# Charger_Control_Board_rev8.net
KiCad netlist of a schematic drawn in EAGLE
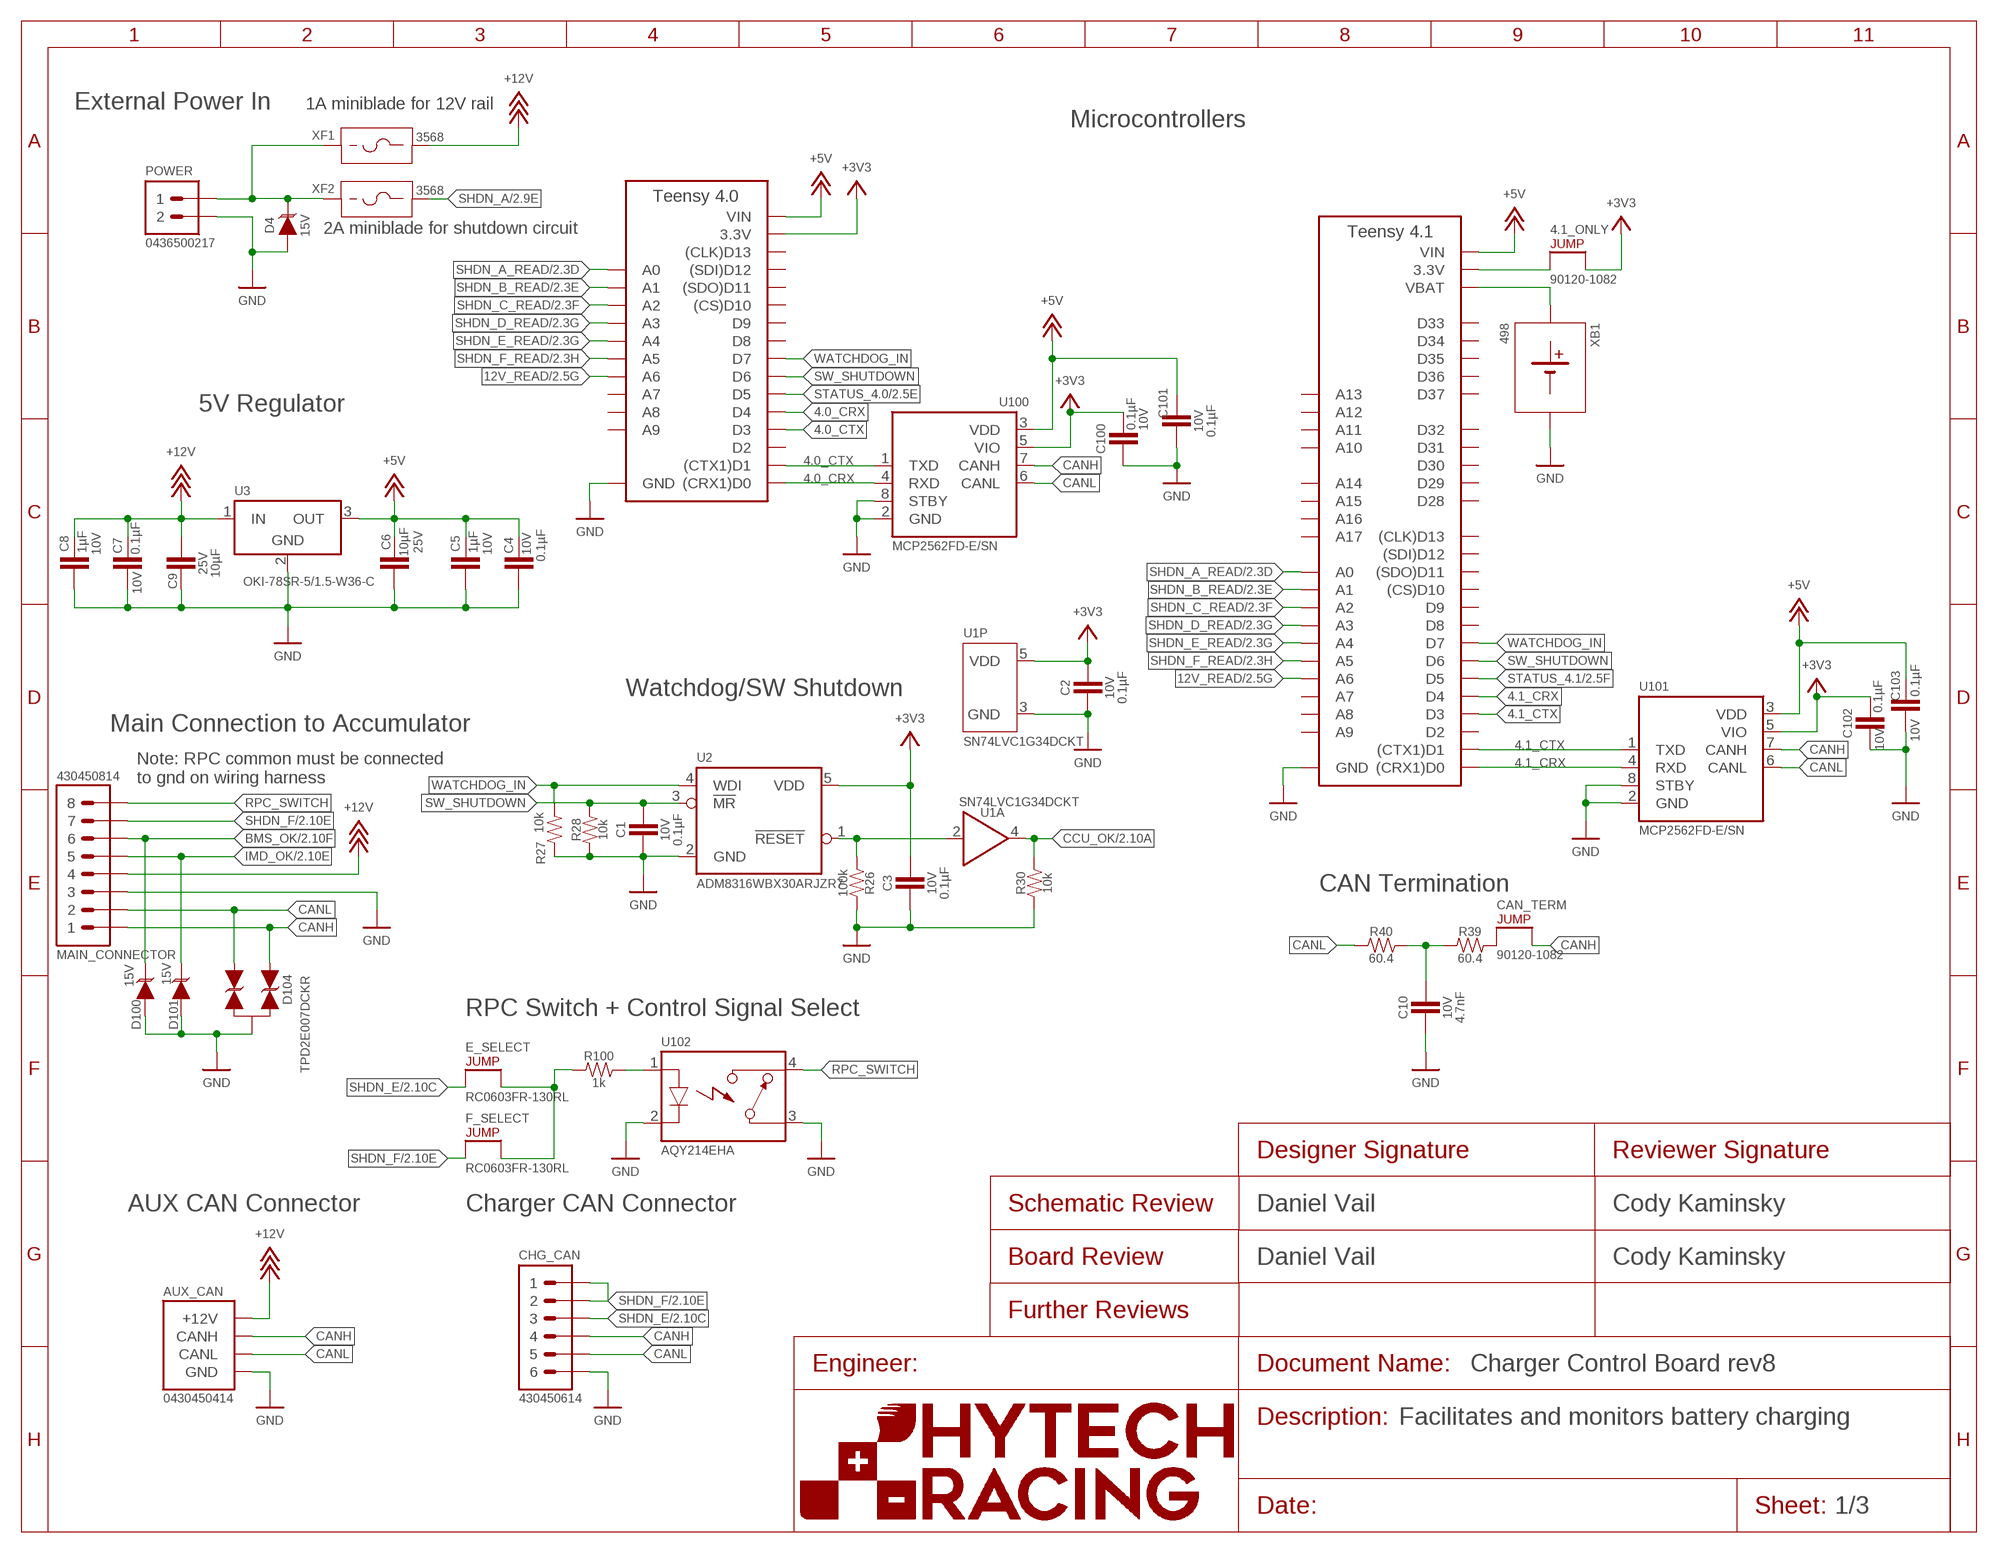
[diagram p0: schematic, sheet 1]
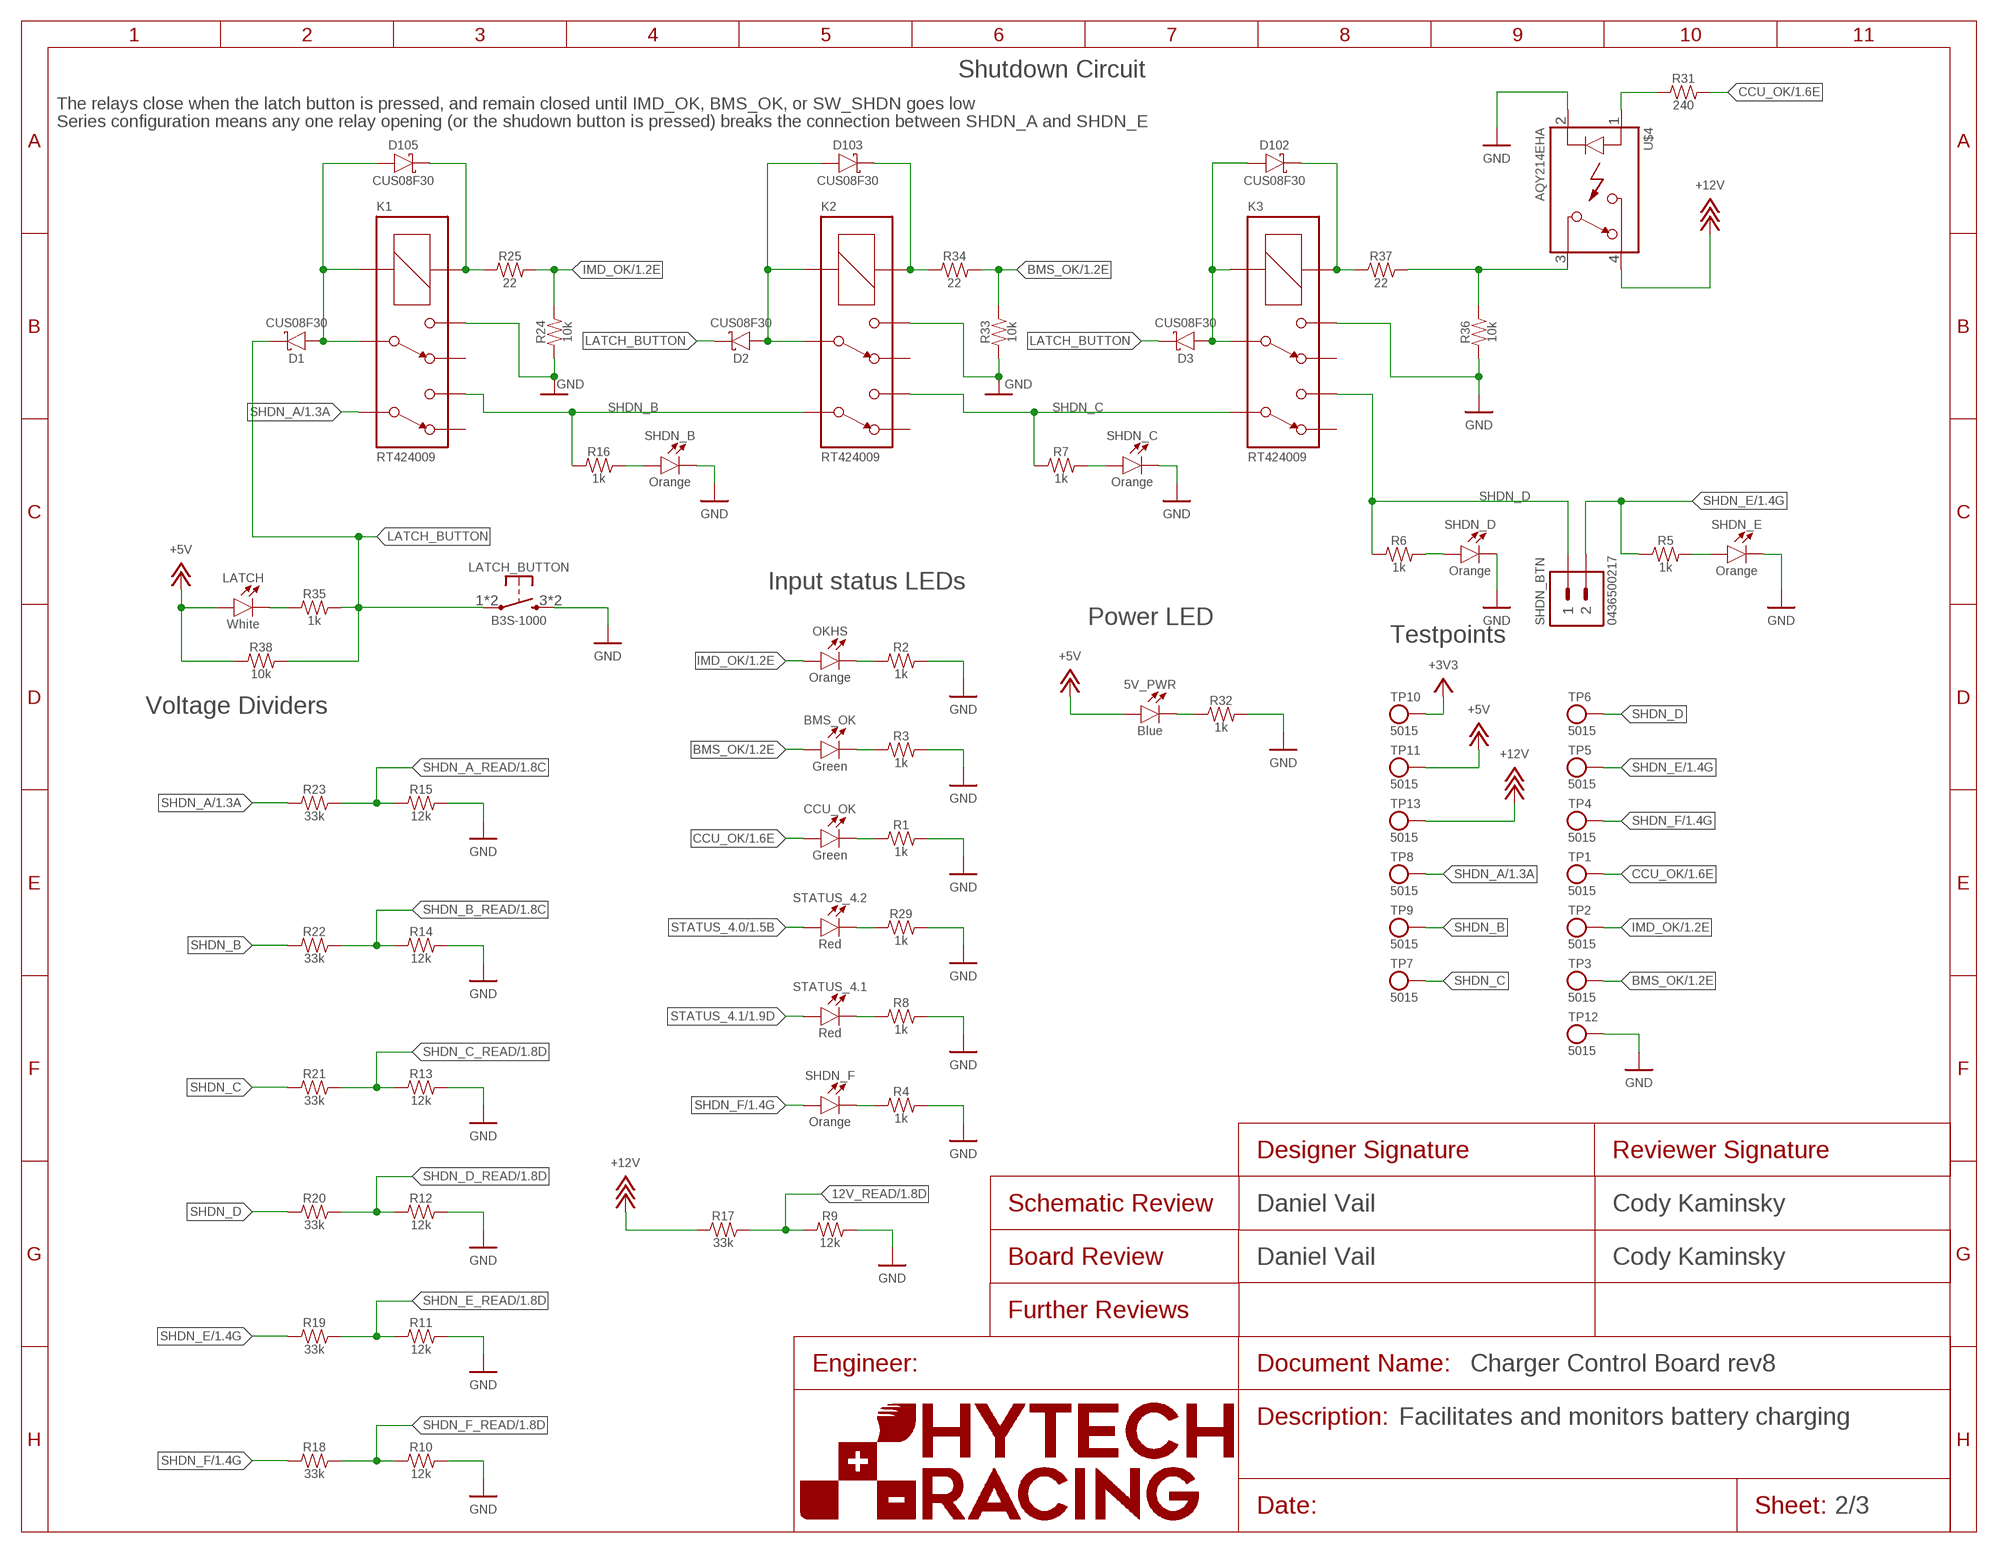
[diagram p1: schematic, sheet 2]
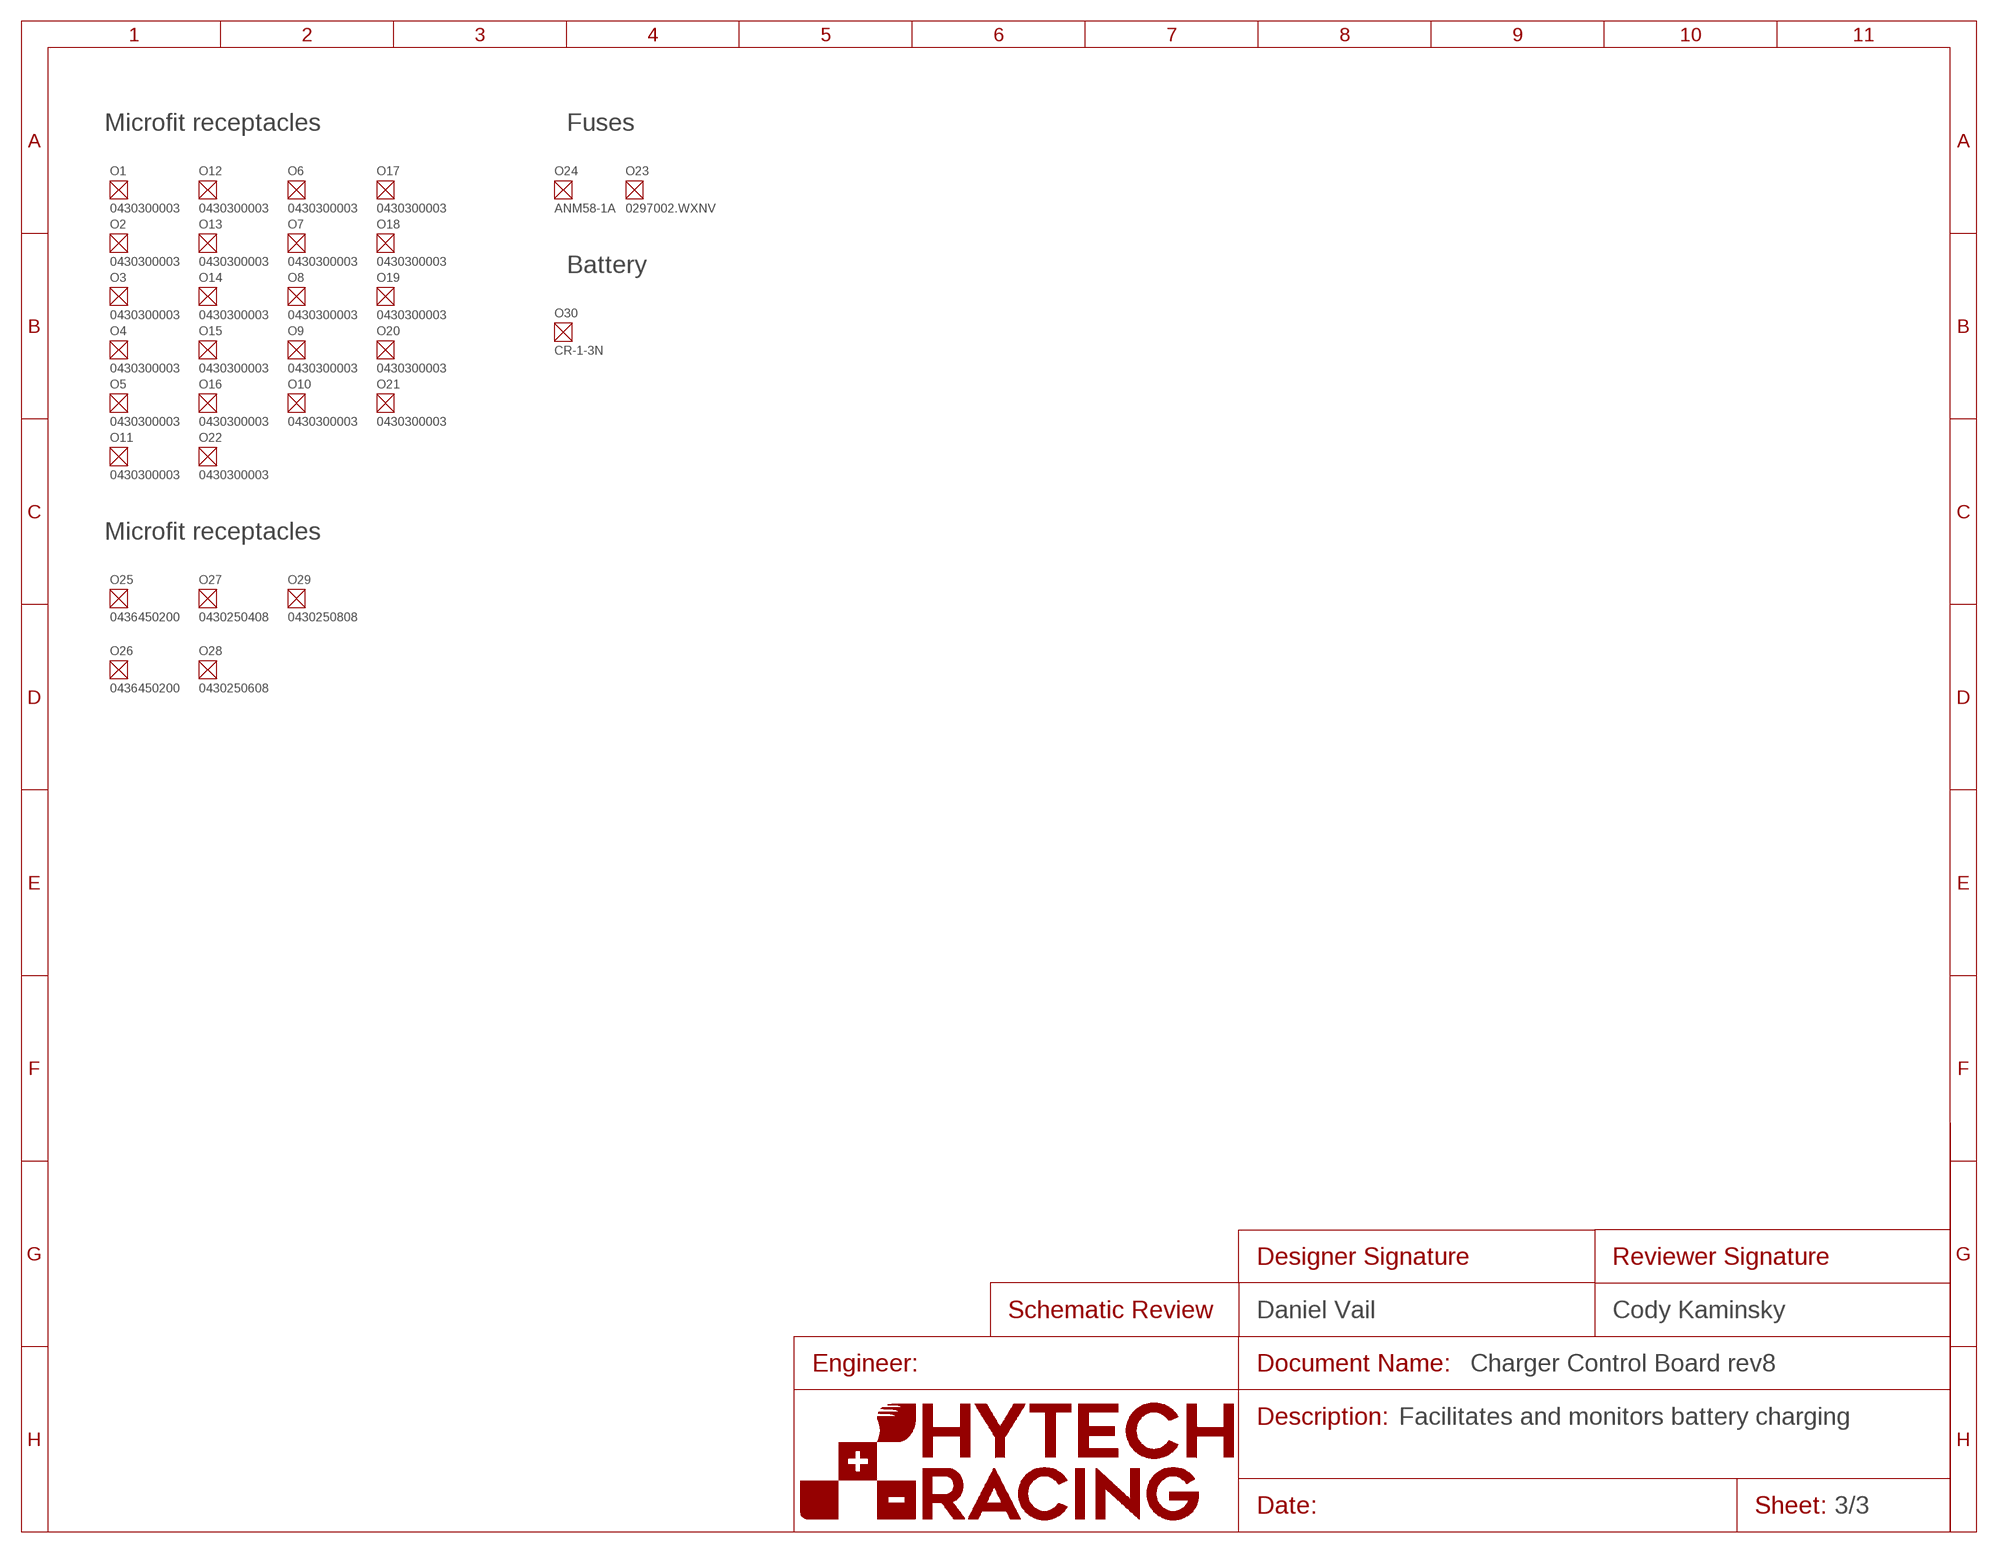
[diagram p2: schematic, sheet 3]

(export (version "E")
  (design (tool "Eeschema 10.0.6"))
  (components
    (comp (ref "5V_PWR")
      (value "LED_0603_BLUE")
      (footprint "eagle-import:0603-LED")
      (fields
        (field (name "COLOR") "Blue")
        (field (name "MANUFACTURER") "Kingbright")
        (field (name "MPN") "APT1608VBC/D")
      )
      (libsource (lib "eagle-import") (part "LED_?_0603BLUE"))
    )
    (comp (ref "BMS_OK")
      (value "LED_0603_GREEN")
      (footprint "eagle-import:0603-LED")
      (fields
        (field (name "COLOR") "Green")
        (field (name "MANUFACTURER") "Kingbright")
        (field (name "MPN") "APT1608ZGCK")
      )
      (libsource (lib "eagle-import") (part "LED_?_0603GREEN"))
    )
    (comp (ref "CCU_OK")
      (value "LED_0603_GREEN")
      (footprint "eagle-import:0603-LED")
      (fields
        (field (name "COLOR") "Green")
        (field (name "MANUFACTURER") "Kingbright")
        (field (name "MPN") "APT1608ZGCK")
      )
      (libsource (lib "eagle-import") (part "LED_?_0603GREEN"))
    )
    (comp (ref "D1")
      (value "SCHOTTKY_SOD323_30V")
      (footprint "eagle-import:SOD-323")
      (fields
        (field (name "MANUFACTURER") "Toshiba Semiconductor and Storage")
        (field (name "MPN") "CUS08F30")
        (field (name "VOLTAGE") "30V")
      )
      (libsource (lib "eagle-import") (part "SCHOTTKY_?_SOD32330V"))
    )
    (comp (ref "D2")
      (value "SCHOTTKY_SOD323_30V")
      (footprint "eagle-import:SOD-323")
      (fields
        (field (name "MANUFACTURER") "Toshiba Semiconductor and Storage")
        (field (name "MPN") "CUS08F30")
        (field (name "VOLTAGE") "30V")
      )
      (libsource (lib "eagle-import") (part "SCHOTTKY_?_SOD32330V"))
    )
    (comp (ref "D3")
      (value "SCHOTTKY_SOD323_30V")
      (footprint "eagle-import:SOD-323")
      (fields
        (field (name "MANUFACTURER") "Toshiba Semiconductor and Storage")
        (field (name "MPN") "CUS08F30")
        (field (name "VOLTAGE") "30V")
      )
      (libsource (lib "eagle-import") (part "SCHOTTKY_?_SOD32330V"))
    )
    (comp (ref "D102")
      (value "SCHOTTKY_SOD323_30V")
      (footprint "eagle-import:SOD-323")
      (fields
        (field (name "MANUFACTURER") "Toshiba Semiconductor and Storage")
        (field (name "MPN") "CUS08F30")
        (field (name "VOLTAGE") "30V")
      )
      (libsource (lib "eagle-import") (part "SCHOTTKY_?_SOD32330V"))
    )
    (comp (ref "D103")
      (value "SCHOTTKY_SOD323_30V")
      (footprint "eagle-import:SOD-323")
      (fields
        (field (name "MANUFACTURER") "Toshiba Semiconductor and Storage")
        (field (name "MPN") "CUS08F30")
        (field (name "VOLTAGE") "30V")
      )
      (libsource (lib "eagle-import") (part "SCHOTTKY_?_SOD32330V"))
    )
    (comp (ref "D105")
      (value "SCHOTTKY_SOD323_30V")
      (footprint "eagle-import:SOD-323")
      (fields
        (field (name "MANUFACTURER") "Toshiba Semiconductor and Storage")
        (field (name "MPN") "CUS08F30")
        (field (name "VOLTAGE") "30V")
      )
      (libsource (lib "eagle-import") (part "SCHOTTKY_?_SOD32330V"))
    )
    (comp (ref "K1")
      (value "RELAY_DPDT")
      (footprint "eagle-import:RT_2_")
      (fields (field (name "MPN") "RT424009") (field (name "MANUFACTURER") "TE Connectivity"))
      (libsource (lib "eagle-import") (part "RELAY_DPDT"))
    )
    (comp (ref "K2")
      (value "RELAY_DPDT")
      (footprint "eagle-import:RT_2_")
      (fields (field (name "MPN") "RT424009") (field (name "MANUFACTURER") "TE Connectivity"))
      (libsource (lib "eagle-import") (part "RELAY_DPDT"))
    )
    (comp (ref "K3")
      (value "RELAY_DPDT")
      (footprint "eagle-import:RT_2_")
      (fields (field (name "MPN") "RT424009") (field (name "MANUFACTURER") "TE Connectivity"))
      (libsource (lib "eagle-import") (part "RELAY_DPDT"))
    )
    (comp (ref "LATCH")
      (value "LED_0603_WHITE")
      (footprint "eagle-import:0603-LED")
      (fields
        (field (name "COLOR") "White")
        (field (name "MANUFACTURER") "Bivar Inc.")
        (field (name "MPN") "SM0603UWC")
      )
      (libsource (lib "eagle-import") (part "LED_?_0603WHITE"))
    )
    (comp (ref "LATCH_BUTTON")
      (value "BUTTON")
      (footprint "eagle-import:B3S-100X")
      (fields (field (name "MPN") "B3S-1000") (field (name "MANUFACTURER") "Omron"))
      (libsource (lib "eagle-import") (part "BUTTON"))
    )
    (comp (ref "OKHS")
      (value "LED_0603_ORANGE")
      (footprint "eagle-import:0603-LED")
      (fields
        (field (name "COLOR") "Orange")
        (field (name "MANUFACTURER") "Kingbright")
        (field (name "MPN") "APT1608SECK")
      )
      (libsource (lib "eagle-import") (part "LED_?_0603ORANGE"))
    )
    (comp (ref "R1")
      (value "RESISTOR_0603_1K")
      (footprint "eagle-import:0603-RES")
      (fields
        (field (name "MANUFACTURER") "Yageo")
        (field (name "MPN") "RC0603FR-071KL")
        (field (name "POWER") "0.1W")
        (field (name "RESISTANCE") "1k")
      )
      (libsource (lib "eagle-import") (part "RESISTOR_?_06031K"))
    )
    (comp (ref "R2")
      (value "RESISTOR_0603_1K")
      (footprint "eagle-import:0603-RES")
      (fields
        (field (name "MANUFACTURER") "Yageo")
        (field (name "MPN") "RC0603FR-071KL")
        (field (name "POWER") "0.1W")
        (field (name "RESISTANCE") "1k")
      )
      (libsource (lib "eagle-import") (part "RESISTOR_?_06031K"))
    )
    (comp (ref "R3")
      (value "RESISTOR_0603_1K")
      (footprint "eagle-import:0603-RES")
      (fields
        (field (name "MANUFACTURER") "Yageo")
        (field (name "MPN") "RC0603FR-071KL")
        (field (name "POWER") "0.1W")
        (field (name "RESISTANCE") "1k")
      )
      (libsource (lib "eagle-import") (part "RESISTOR_?_06031K"))
    )
    (comp (ref "R4")
      (value "RESISTOR_0603_1K")
      (footprint "eagle-import:0603-RES")
      (fields
        (field (name "MANUFACTURER") "Yageo")
        (field (name "MPN") "RC0603FR-071KL")
        (field (name "POWER") "0.1W")
        (field (name "RESISTANCE") "1k")
      )
      (libsource (lib "eagle-import") (part "RESISTOR_?_06031K"))
    )
    (comp (ref "R5")
      (value "RESISTOR_0603_1K")
      (footprint "eagle-import:0603-RES")
      (fields
        (field (name "MANUFACTURER") "Yageo")
        (field (name "MPN") "RC0603FR-071KL")
        (field (name "POWER") "0.1W")
        (field (name "RESISTANCE") "1k")
      )
      (libsource (lib "eagle-import") (part "RESISTOR_?_06031K"))
    )
    (comp (ref "R6")
      (value "RESISTOR_0603_1K")
      (footprint "eagle-import:0603-RES")
      (fields
        (field (name "MANUFACTURER") "Yageo")
        (field (name "MPN") "RC0603FR-071KL")
        (field (name "POWER") "0.1W")
        (field (name "RESISTANCE") "1k")
      )
      (libsource (lib "eagle-import") (part "RESISTOR_?_06031K"))
    )
    (comp (ref "R7")
      (value "RESISTOR_0603_1K")
      (footprint "eagle-import:0603-RES")
      (fields
        (field (name "MANUFACTURER") "Yageo")
        (field (name "MPN") "RC0603FR-071KL")
        (field (name "POWER") "0.1W")
        (field (name "RESISTANCE") "1k")
      )
      (libsource (lib "eagle-import") (part "RESISTOR_?_06031K"))
    )
    (comp (ref "R8")
      (value "RESISTOR_0603_1K")
      (footprint "eagle-import:0603-RES")
      (fields
        (field (name "MANUFACTURER") "Yageo")
        (field (name "MPN") "RC0603FR-071KL")
        (field (name "POWER") "0.1W")
        (field (name "RESISTANCE") "1k")
      )
      (libsource (lib "eagle-import") (part "RESISTOR_?_06031K"))
    )
    (comp (ref "R9")
      (value "RESISTOR_0603_12K")
      (footprint "eagle-import:0603-RES")
      (fields
        (field (name "MANUFACTURER") "Yageo")
        (field (name "MPN") "RC0603FR-0712KL")
        (field (name "POWER") "0.1W")
        (field (name "RESISTANCE") "12k")
      )
      (libsource (lib "eagle-import") (part "RESISTOR_?_060312K"))
    )
    (comp (ref "R10")
      (value "RESISTOR_0603_12K")
      (footprint "eagle-import:0603-RES")
      (fields
        (field (name "MANUFACTURER") "Yageo")
        (field (name "MPN") "RC0603FR-0712KL")
        (field (name "POWER") "0.1W")
        (field (name "RESISTANCE") "12k")
      )
      (libsource (lib "eagle-import") (part "RESISTOR_?_060312K"))
    )
    (comp (ref "R11")
      (value "RESISTOR_0603_12K")
      (footprint "eagle-import:0603-RES")
      (fields
        (field (name "MANUFACTURER") "Yageo")
        (field (name "MPN") "RC0603FR-0712KL")
        (field (name "POWER") "0.1W")
        (field (name "RESISTANCE") "12k")
      )
      (libsource (lib "eagle-import") (part "RESISTOR_?_060312K"))
    )
    (comp (ref "R12")
      (value "RESISTOR_0603_12K")
      (footprint "eagle-import:0603-RES")
      (fields
        (field (name "MANUFACTURER") "Yageo")
        (field (name "MPN") "RC0603FR-0712KL")
        (field (name "POWER") "0.1W")
        (field (name "RESISTANCE") "12k")
      )
      (libsource (lib "eagle-import") (part "RESISTOR_?_060312K"))
    )
    (comp (ref "R13")
      (value "RESISTOR_0603_12K")
      (footprint "eagle-import:0603-RES")
      (fields
        (field (name "MANUFACTURER") "Yageo")
        (field (name "MPN") "RC0603FR-0712KL")
        (field (name "POWER") "0.1W")
        (field (name "RESISTANCE") "12k")
      )
      (libsource (lib "eagle-import") (part "RESISTOR_?_060312K"))
    )
    (comp (ref "R14")
      (value "RESISTOR_0603_12K")
      (footprint "eagle-import:0603-RES")
      (fields
        (field (name "MANUFACTURER") "Yageo")
        (field (name "MPN") "RC0603FR-0712KL")
        (field (name "POWER") "0.1W")
        (field (name "RESISTANCE") "12k")
      )
      (libsource (lib "eagle-import") (part "RESISTOR_?_060312K"))
    )
    (comp (ref "R15")
      (value "RESISTOR_0603_12K")
      (footprint "eagle-import:0603-RES")
      (fields
        (field (name "MANUFACTURER") "Yageo")
        (field (name "MPN") "RC0603FR-0712KL")
        (field (name "POWER") "0.1W")
        (field (name "RESISTANCE") "12k")
      )
      (libsource (lib "eagle-import") (part "RESISTOR_?_060312K"))
    )
    (comp (ref "R16")
      (value "RESISTOR_0603_1K")
      (footprint "eagle-import:0603-RES")
      (fields
        (field (name "MANUFACTURER") "Yageo")
        (field (name "MPN") "RC0603FR-071KL")
        (field (name "POWER") "0.1W")
        (field (name "RESISTANCE") "1k")
      )
      (libsource (lib "eagle-import") (part "RESISTOR_?_06031K"))
    )
    (comp (ref "R17")
      (value "RESISTOR_0603_33K")
      (footprint "eagle-import:0603-RES")
      (fields
        (field (name "MANUFACTURER") "Yageo")
        (field (name "MPN") "RC0603FR-0733KL")
        (field (name "POWER") "0.1W")
        (field (name "RESISTANCE") "33k")
      )
      (libsource (lib "eagle-import") (part "RESISTOR_?_060333K"))
    )
    (comp (ref "R18")
      (value "RESISTOR_0603_33K")
      (footprint "eagle-import:0603-RES")
      (fields
        (field (name "MANUFACTURER") "Yageo")
        (field (name "MPN") "RC0603FR-0733KL")
        (field (name "POWER") "0.1W")
        (field (name "RESISTANCE") "33k")
      )
      (libsource (lib "eagle-import") (part "RESISTOR_?_060333K"))
    )
    (comp (ref "R19")
      (value "RESISTOR_0603_33K")
      (footprint "eagle-import:0603-RES")
      (fields
        (field (name "MANUFACTURER") "Yageo")
        (field (name "MPN") "RC0603FR-0733KL")
        (field (name "POWER") "0.1W")
        (field (name "RESISTANCE") "33k")
      )
      (libsource (lib "eagle-import") (part "RESISTOR_?_060333K"))
    )
    (comp (ref "R20")
      (value "RESISTOR_0603_33K")
      (footprint "eagle-import:0603-RES")
      (fields
        (field (name "MANUFACTURER") "Yageo")
        (field (name "MPN") "RC0603FR-0733KL")
        (field (name "POWER") "0.1W")
        (field (name "RESISTANCE") "33k")
      )
      (libsource (lib "eagle-import") (part "RESISTOR_?_060333K"))
    )
    (comp (ref "R21")
      (value "RESISTOR_0603_33K")
      (footprint "eagle-import:0603-RES")
      (fields
        (field (name "MANUFACTURER") "Yageo")
        (field (name "MPN") "RC0603FR-0733KL")
        (field (name "POWER") "0.1W")
        (field (name "RESISTANCE") "33k")
      )
      (libsource (lib "eagle-import") (part "RESISTOR_?_060333K"))
    )
    (comp (ref "R22")
      (value "RESISTOR_0603_33K")
      (footprint "eagle-import:0603-RES")
      (fields
        (field (name "MANUFACTURER") "Yageo")
        (field (name "MPN") "RC0603FR-0733KL")
        (field (name "POWER") "0.1W")
        (field (name "RESISTANCE") "33k")
      )
      (libsource (lib "eagle-import") (part "RESISTOR_?_060333K"))
    )
    (comp (ref "R23")
      (value "RESISTOR_0603_33K")
      (footprint "eagle-import:0603-RES")
      (fields
        (field (name "MANUFACTURER") "Yageo")
        (field (name "MPN") "RC0603FR-0733KL")
        (field (name "POWER") "0.1W")
        (field (name "RESISTANCE") "33k")
      )
      (libsource (lib "eagle-import") (part "RESISTOR_?_060333K"))
    )
    (comp (ref "R24")
      (value "RESISTOR_0603_10K")
      (footprint "eagle-import:0603-RES")
      (fields
        (field (name "MANUFACTURER") "Yageo")
        (field (name "MPN") "RC0603FR-0710KL")
        (field (name "POWER") "0.1W")
        (field (name "RESISTANCE") "10k")
      )
      (libsource (lib "eagle-import") (part "RESISTOR_?_060310K"))
    )
    (comp (ref "R25")
      (value "RESISTOR_0603_22")
      (footprint "eagle-import:0603-RES")
      (fields
        (field (name "MANUFACTURER") "Yageo")
        (field (name "MPN") "RC0603FR-0722RL")
        (field (name "POWER") "0.1W")
        (field (name "RESISTANCE") "22")
      )
      (libsource (lib "eagle-import") (part "RESISTOR_?_060322"))
    )
    (comp (ref "R29")
      (value "RESISTOR_0603_1K")
      (footprint "eagle-import:0603-RES")
      (fields
        (field (name "MANUFACTURER") "Yageo")
        (field (name "MPN") "RC0603FR-071KL")
        (field (name "POWER") "0.1W")
        (field (name "RESISTANCE") "1k")
      )
      (libsource (lib "eagle-import") (part "RESISTOR_?_06031K"))
    )
    (comp (ref "R31")
      (value "RESISTOR_0603_240")
      (footprint "eagle-import:0603-RES")
      (fields
        (field (name "MANUFACTURER") "Yageo")
        (field (name "MPN") "RC0603FR-07240RL")
        (field (name "POWER") "0.1W")
        (field (name "RESISTANCE") "240")
      )
      (libsource (lib "eagle-import") (part "RESISTOR_?_0603240"))
    )
    (comp (ref "R32")
      (value "RESISTOR_0603_1K")
      (footprint "eagle-import:0603-RES")
      (fields
        (field (name "MANUFACTURER") "Yageo")
        (field (name "MPN") "RC0603FR-071KL")
        (field (name "POWER") "0.1W")
        (field (name "RESISTANCE") "1k")
      )
      (libsource (lib "eagle-import") (part "RESISTOR_?_06031K"))
    )
    (comp (ref "R33")
      (value "RESISTOR_0603_10K")
      (footprint "eagle-import:0603-RES")
      (fields
        (field (name "MANUFACTURER") "Yageo")
        (field (name "MPN") "RC0603FR-0710KL")
        (field (name "POWER") "0.1W")
        (field (name "RESISTANCE") "10k")
      )
      (libsource (lib "eagle-import") (part "RESISTOR_?_060310K"))
    )
    (comp (ref "R34")
      (value "RESISTOR_0603_22")
      (footprint "eagle-import:0603-RES")
      (fields
        (field (name "MANUFACTURER") "Yageo")
        (field (name "MPN") "RC0603FR-0722RL")
        (field (name "POWER") "0.1W")
        (field (name "RESISTANCE") "22")
      )
      (libsource (lib "eagle-import") (part "RESISTOR_?_060322"))
    )
    (comp (ref "R35")
      (value "RESISTOR_0603_1K")
      (footprint "eagle-import:0603-RES")
      (fields
        (field (name "MANUFACTURER") "Yageo")
        (field (name "MPN") "RC0603FR-071KL")
        (field (name "POWER") "0.1W")
        (field (name "RESISTANCE") "1k")
      )
      (libsource (lib "eagle-import") (part "RESISTOR_?_06031K"))
    )
    (comp (ref "R36")
      (value "RESISTOR_0603_10K")
      (footprint "eagle-import:0603-RES")
      (fields
        (field (name "MANUFACTURER") "Yageo")
        (field (name "MPN") "RC0603FR-0710KL")
        (field (name "POWER") "0.1W")
        (field (name "RESISTANCE") "10k")
      )
      (libsource (lib "eagle-import") (part "RESISTOR_?_060310K"))
    )
    (comp (ref "R37")
      (value "RESISTOR_0603_22")
      (footprint "eagle-import:0603-RES")
      (fields
        (field (name "MANUFACTURER") "Yageo")
        (field (name "MPN") "RC0603FR-0722RL")
        (field (name "POWER") "0.1W")
        (field (name "RESISTANCE") "22")
      )
      (libsource (lib "eagle-import") (part "RESISTOR_?_060322"))
    )
    (comp (ref "R38")
      (value "RESISTOR_0603_10K")
      (footprint "eagle-import:0603-RES")
      (fields
        (field (name "MANUFACTURER") "Yageo")
        (field (name "MPN") "RC0603FR-0710KL")
        (field (name "POWER") "0.1W")
        (field (name "RESISTANCE") "10k")
      )
      (libsource (lib "eagle-import") (part "RESISTOR_?_060310K"))
    )
    (comp (ref "SHDN_B")
      (value "LED_0603_ORANGE")
      (footprint "eagle-import:0603-LED")
      (fields
        (field (name "COLOR") "Orange")
        (field (name "MANUFACTURER") "Kingbright")
        (field (name "MPN") "APT1608SECK")
      )
      (libsource (lib "eagle-import") (part "LED_?_0603ORANGE"))
    )
    (comp (ref "SHDN_BTN")
      (value "CONNECTOR-2_MF_T_V_")
      (footprint "eagle-import:MOLEX_MICROFIT_PTH_VERTICAL_02_SINGLE")
      (fields (field (name "MANUFACTURER") "Molex") (field (name "MPN") "0436500217"))
      (libsource (lib "eagle-import") (part "CONNECTOR-2_?_MF_T_VBLACK"))
    )
    (comp (ref "SHDN_C")
      (value "LED_0603_ORANGE")
      (footprint "eagle-import:0603-LED")
      (fields
        (field (name "COLOR") "Orange")
        (field (name "MANUFACTURER") "Kingbright")
        (field (name "MPN") "APT1608SECK")
      )
      (libsource (lib "eagle-import") (part "LED_?_0603ORANGE"))
    )
    (comp (ref "SHDN_D")
      (value "LED_0603_ORANGE")
      (footprint "eagle-import:0603-LED")
      (fields
        (field (name "COLOR") "Orange")
        (field (name "MANUFACTURER") "Kingbright")
        (field (name "MPN") "APT1608SECK")
      )
      (libsource (lib "eagle-import") (part "LED_?_0603ORANGE"))
    )
    (comp (ref "SHDN_E")
      (value "LED_0603_ORANGE")
      (footprint "eagle-import:0603-LED")
      (fields
        (field (name "COLOR") "Orange")
        (field (name "MANUFACTURER") "Kingbright")
        (field (name "MPN") "APT1608SECK")
      )
      (libsource (lib "eagle-import") (part "LED_?_0603ORANGE"))
    )
    (comp (ref "SHDN_F")
      (value "LED_0603_ORANGE")
      (footprint "eagle-import:0603-LED")
      (fields
        (field (name "COLOR") "Orange")
        (field (name "MANUFACTURER") "Kingbright")
        (field (name "MPN") "APT1608SECK")
      )
      (libsource (lib "eagle-import") (part "LED_?_0603ORANGE"))
    )
    (comp (ref "STATUS_4.1")
      (value "LED_0603_RED")
      (footprint "eagle-import:0603-LED")
      (fields
        (field (name "COLOR") "Red")
        (field (name "MANUFACTURER") "Kingbright")
        (field (name "MPN") "APT1608SECK/J3-PRV")
      )
      (libsource (lib "eagle-import") (part "LED_?_0603RED"))
    )
    (comp (ref "STATUS_4.2")
      (value "LED_0603_RED")
      (footprint "eagle-import:0603-LED")
      (fields
        (field (name "COLOR") "Red")
        (field (name "MANUFACTURER") "Kingbright")
        (field (name "MPN") "APT1608SECK/J3-PRV")
      )
      (libsource (lib "eagle-import") (part "LED_?_0603RED"))
    )
    (comp (ref "TP1")
      (value "TEST_POINT")
      (footprint "eagle-import:5015")
      (fields (field (name "MPN") "5015") (field (name "MANUFACTURER") "Keystone Electronics"))
      (libsource (lib "eagle-import") (part "TEST_POINT"))
    )
    (comp (ref "TP2")
      (value "TEST_POINT")
      (footprint "eagle-import:5015")
      (fields (field (name "MPN") "5015") (field (name "MANUFACTURER") "Keystone Electronics"))
      (libsource (lib "eagle-import") (part "TEST_POINT"))
    )
    (comp (ref "TP3")
      (value "TEST_POINT")
      (footprint "eagle-import:5015")
      (fields (field (name "MPN") "5015") (field (name "MANUFACTURER") "Keystone Electronics"))
      (libsource (lib "eagle-import") (part "TEST_POINT"))
    )
    (comp (ref "TP4")
      (value "TEST_POINT")
      (footprint "eagle-import:5015")
      (fields (field (name "MPN") "5015") (field (name "MANUFACTURER") "Keystone Electronics"))
      (libsource (lib "eagle-import") (part "TEST_POINT"))
    )
    (comp (ref "TP5")
      (value "TEST_POINT")
      (footprint "eagle-import:5015")
      (fields (field (name "MPN") "5015") (field (name "MANUFACTURER") "Keystone Electronics"))
      (libsource (lib "eagle-import") (part "TEST_POINT"))
    )
    (comp (ref "TP6")
      (value "TEST_POINT")
      (footprint "eagle-import:5015")
      (fields (field (name "MPN") "5015") (field (name "MANUFACTURER") "Keystone Electronics"))
      (libsource (lib "eagle-import") (part "TEST_POINT"))
    )
    (comp (ref "TP7")
      (value "TEST_POINT")
      (footprint "eagle-import:5015")
      (fields (field (name "MPN") "5015") (field (name "MANUFACTURER") "Keystone Electronics"))
      (libsource (lib "eagle-import") (part "TEST_POINT"))
    )
    (comp (ref "TP8")
      (value "TEST_POINT")
      (footprint "eagle-import:5015")
      (fields (field (name "MPN") "5015") (field (name "MANUFACTURER") "Keystone Electronics"))
      (libsource (lib "eagle-import") (part "TEST_POINT"))
    )
    (comp (ref "TP9")
      (value "TEST_POINT")
      (footprint "eagle-import:5015")
      (fields (field (name "MPN") "5015") (field (name "MANUFACTURER") "Keystone Electronics"))
      (libsource (lib "eagle-import") (part "TEST_POINT"))
    )
    (comp (ref "TP10")
      (value "TEST_POINT")
      (footprint "eagle-import:5015")
      (fields (field (name "MPN") "5015") (field (name "MANUFACTURER") "Keystone Electronics"))
      (libsource (lib "eagle-import") (part "TEST_POINT"))
    )
    (comp (ref "TP11")
      (value "TEST_POINT")
      (footprint "eagle-import:5015")
      (fields (field (name "MPN") "5015") (field (name "MANUFACTURER") "Keystone Electronics"))
      (libsource (lib "eagle-import") (part "TEST_POINT"))
    )
    (comp (ref "TP12")
      (value "TEST_POINT")
      (footprint "eagle-import:5015")
      (fields (field (name "MPN") "5015") (field (name "MANUFACTURER") "Keystone Electronics"))
      (libsource (lib "eagle-import") (part "TEST_POINT"))
    )
    (comp (ref "TP13")
      (value "TEST_POINT")
      (footprint "eagle-import:5015")
      (fields (field (name "MPN") "5015") (field (name "MANUFACTURER") "Keystone Electronics"))
      (libsource (lib "eagle-import") (part "TEST_POINT"))
    )
    (comp (ref "U$4")
      (value "RELAY_SOLIDSTATE_NO")
      (footprint "eagle-import:DIP-4")
      (fields (field (name "MPN") "AQY214EHA") (field (name "MANUFACTURER") "AQY214EHA"))
      (libsource (lib "eagle-import") (part "RELAY_SOLIDSTATE_NO"))
    )
    (comp (ref "4.1_ONLY")
      (value "JUMPER__1X02")
      (footprint "eagle-import:1X02")
      (fields (field (name "MANUFACTURER") "Molex") (field (name "MPN") "90120-1082 "))
      (libsource (lib "eagle-import") (part "JUMPER_?_1X02"))
    )
    (comp (ref "A1")
      (value "TEENSY_4.1")
      (footprint "eagle-import:TEENSY_LONG_EXT")
      (libsource (lib "eagle-import") (part "TEENSY_4.1"))
    )
    (comp (ref "A2")
      (value "TEENSY_4.0")
      (footprint "eagle-import:TEENSY_SHORT")
      (libsource (lib "eagle-import") (part "TEENSY_4.0"))
    )
    (comp (ref "AUX_CAN")
      (value "CONNECTOR-CAN_MF_T_V_BLACK")
      (footprint "eagle-import:MOLEX_MICROFIT_PTH_VERTICAL_04_DUAL")
      (fields (field (name "MANUFACTURER") "Molex") (field (name "MPN") "0430450414"))
      (libsource (lib "eagle-import") (part "CONNECTOR-CAN_?_MF_T_VBLACK"))
    )
    (comp (ref "C1")
      (value "CAPACITOR_0603_10V_0.1UF")
      (footprint "eagle-import:0603-CAP")
      (fields
        (field (name "CAPACITANCE") "0.1µF")
        (field (name "MANUFACTURER") "Vishay Vitramon")
        (field (name "MPN") "VJ0603Y104JXQPW1BC")
        (field (name "TOLERANCE") "5%")
        (field (name "VOLTAGE") "10V")
      )
      (libsource (lib "eagle-import") (part "CAPACITOR_?_060310V_0.1UF"))
    )
    (comp (ref "C2")
      (value "CAPACITOR_0603_10V_0.1UF")
      (footprint "eagle-import:0603-CAP")
      (fields
        (field (name "CAPACITANCE") "0.1µF")
        (field (name "MANUFACTURER") "Vishay Vitramon")
        (field (name "MPN") "VJ0603Y104JXQPW1BC")
        (field (name "TOLERANCE") "5%")
        (field (name "VOLTAGE") "10V")
      )
      (libsource (lib "eagle-import") (part "CAPACITOR_?_060310V_0.1UF"))
    )
    (comp (ref "C3")
      (value "CAPACITOR_0603_10V_0.1UF")
      (footprint "eagle-import:0603-CAP")
      (fields
        (field (name "CAPACITANCE") "0.1µF")
        (field (name "MANUFACTURER") "Vishay Vitramon")
        (field (name "MPN") "VJ0603Y104JXQPW1BC")
        (field (name "TOLERANCE") "5%")
        (field (name "VOLTAGE") "10V")
      )
      (libsource (lib "eagle-import") (part "CAPACITOR_?_060310V_0.1UF"))
    )
    (comp (ref "C4")
      (value "CAPACITOR_0603_10V_0.1UF")
      (footprint "eagle-import:0603-CAP")
      (fields
        (field (name "CAPACITANCE") "0.1µF")
        (field (name "MANUFACTURER") "Vishay Vitramon")
        (field (name "MPN") "VJ0603Y104JXQPW1BC")
        (field (name "TOLERANCE") "5%")
        (field (name "VOLTAGE") "10V")
      )
      (libsource (lib "eagle-import") (part "CAPACITOR_?_060310V_0.1UF"))
    )
    (comp (ref "C5")
      (value "CAPACITOR_0603_10V_1UF")
      (footprint "eagle-import:0603-CAP")
      (fields
        (field (name "CAPACITANCE") "1µF")
        (field (name "MANUFACTURER") "Yageo")
        (field (name "MPN") "CC0603KRX7R6BB105")
        (field (name "TOLERANCE") "10%")
        (field (name "VOLTAGE") "10V")
      )
      (libsource (lib "eagle-import") (part "CAPACITOR_?_060310V_1UF"))
    )
    (comp (ref "C6")
      (value "CAPACITOR_0603_25V_10UF")
      (footprint "eagle-import:0603-CAP")
      (fields
        (field (name "CAPACITANCE") "10µF")
        (field (name "MANUFACTURER") "Murata Electronics")
        (field (name "MPN") "GRM188R61E106MA73D")
        (field (name "TOLERANCE") "20%")
        (field (name "VOLTAGE") "25V")
      )
      (libsource (lib "eagle-import") (part "CAPACITOR_?_060325V_10UF"))
    )
    (comp (ref "C7")
      (value "CAPACITOR_0603_10V_0.1UF")
      (footprint "eagle-import:0603-CAP")
      (fields
        (field (name "CAPACITANCE") "0.1µF")
        (field (name "MANUFACTURER") "Vishay Vitramon")
        (field (name "MPN") "VJ0603Y104JXQPW1BC")
        (field (name "TOLERANCE") "5%")
        (field (name "VOLTAGE") "10V")
      )
      (libsource (lib "eagle-import") (part "CAPACITOR_?_060310V_0.1UF"))
    )
    (comp (ref "C8")
      (value "CAPACITOR_0603_10V_1UF")
      (footprint "eagle-import:0603-CAP")
      (fields
        (field (name "CAPACITANCE") "1µF")
        (field (name "MANUFACTURER") "Yageo")
        (field (name "MPN") "CC0603KRX7R6BB105")
        (field (name "TOLERANCE") "10%")
        (field (name "VOLTAGE") "10V")
      )
      (libsource (lib "eagle-import") (part "CAPACITOR_?_060310V_1UF"))
    )
    (comp (ref "C9")
      (value "CAPACITOR_0603_25V_10UF")
      (footprint "eagle-import:0603-CAP")
      (fields
        (field (name "CAPACITANCE") "10µF")
        (field (name "MANUFACTURER") "Murata Electronics")
        (field (name "MPN") "GRM188R61E106MA73D")
        (field (name "TOLERANCE") "20%")
        (field (name "VOLTAGE") "25V")
      )
      (libsource (lib "eagle-import") (part "CAPACITOR_?_060325V_10UF"))
    )
    (comp (ref "C10")
      (value "CAPACITOR_0603_10V_4.7NF")
      (footprint "eagle-import:0603-CAP")
      (fields
        (field (name "CAPACITANCE") "4.7nF")
        (field (name "MANUFACTURER") "Würth Elektronik")
        (field (name "MPN") "885012206012")
        (field (name "TOLERANCE") "10%")
        (field (name "VOLTAGE") "10V")
      )
      (libsource (lib "eagle-import") (part "CAPACITOR_?_060310V_4.7NF"))
    )
    (comp (ref "C100")
      (value "CAPACITOR_0603_10V_0.1UF")
      (footprint "eagle-import:0603-CAP")
      (fields
        (field (name "CAPACITANCE") "0.1µF")
        (field (name "MANUFACTURER") "Vishay Vitramon")
        (field (name "MPN") "VJ0603Y104JXQPW1BC")
        (field (name "TOLERANCE") "5%")
        (field (name "VOLTAGE") "10V")
      )
      (libsource (lib "eagle-import") (part "CAPACITOR_?_060310V_0.1UF"))
    )
    (comp (ref "C101")
      (value "CAPACITOR_0603_10V_0.1UF")
      (footprint "eagle-import:0603-CAP")
      (fields
        (field (name "CAPACITANCE") "0.1µF")
        (field (name "MANUFACTURER") "Vishay Vitramon")
        (field (name "MPN") "VJ0603Y104JXQPW1BC")
        (field (name "TOLERANCE") "5%")
        (field (name "VOLTAGE") "10V")
      )
      (libsource (lib "eagle-import") (part "CAPACITOR_?_060310V_0.1UF"))
    )
    (comp (ref "C102")
      (value "CAPACITOR_0603_10V_0.1UF")
      (footprint "eagle-import:0603-CAP")
      (fields
        (field (name "CAPACITANCE") "0.1µF")
        (field (name "MANUFACTURER") "Vishay Vitramon")
        (field (name "MPN") "VJ0603Y104JXQPW1BC")
        (field (name "TOLERANCE") "5%")
        (field (name "VOLTAGE") "10V")
      )
      (libsource (lib "eagle-import") (part "CAPACITOR_?_060310V_0.1UF"))
    )
    (comp (ref "C103")
      (value "CAPACITOR_0603_10V_0.1UF")
      (footprint "eagle-import:0603-CAP")
      (fields
        (field (name "CAPACITANCE") "0.1µF")
        (field (name "MANUFACTURER") "Vishay Vitramon")
        (field (name "MPN") "VJ0603Y104JXQPW1BC")
        (field (name "TOLERANCE") "5%")
        (field (name "VOLTAGE") "10V")
      )
      (libsource (lib "eagle-import") (part "CAPACITOR_?_060310V_0.1UF"))
    )
    (comp (ref "CAN_TERM")
      (value "JUMPER__1X02")
      (footprint "eagle-import:1X02")
      (fields (field (name "MANUFACTURER") "Molex") (field (name "MPN") "90120-1082 "))
      (libsource (lib "eagle-import") (part "JUMPER_?_1X02"))
    )
    (comp (ref "CHG_CAN")
      (value "CONNECTOR-6_MF_T_V_BLACK")
      (footprint "eagle-import:MOLEX_MICROFIT_PTH_VERTICAL_06_DUAL")
      (fields (field (name "MANUFACTURER") "Molex") (field (name "MPN") "430450614"))
      (libsource (lib "eagle-import") (part "CONNECTOR-6_?_MF_T_VBLACK"))
    )
    (comp (ref "D4")
      (value "TVS_15V")
      (footprint "eagle-import:SOT-23")
      (fields
        (field (name "MANUFACTURER") "Vishay General Semiconductor - Diodes Division")
        (field (name "MPN") "GSOT15-E3-08")
        (field (name "VOLTAGE") "15V")
      )
      (libsource (lib "eagle-import") (part "TVS_15V"))
    )
    (comp (ref "D100")
      (value "TVS_15V")
      (footprint "eagle-import:SOT-23")
      (fields
        (field (name "MANUFACTURER") "Vishay General Semiconductor - Diodes Division")
        (field (name "MPN") "GSOT15-E3-08")
        (field (name "VOLTAGE") "15V")
      )
      (libsource (lib "eagle-import") (part "TVS_15V"))
    )
    (comp (ref "D101")
      (value "TVS_15V")
      (footprint "eagle-import:SOT-23")
      (fields
        (field (name "MANUFACTURER") "Vishay General Semiconductor - Diodes Division")
        (field (name "MPN") "GSOT15-E3-08")
        (field (name "VOLTAGE") "15V")
      )
      (libsource (lib "eagle-import") (part "TVS_15V"))
    )
    (comp (ref "D104")
      (value "TVS_BIDIRECTIONAL_DUAL")
      (footprint "eagle-import:SC-70-3")
      (fields (field (name "MPN") "TPD2E007DCKR") (field (name "MANUFACTURER") "Texas Instruments"))
      (libsource (lib "eagle-import") (part "TVS_BIDIRECTIONAL_DUAL"))
    )
    (comp (ref "E_SELECT")
      (value "JUMPER_0603_")
      (footprint "eagle-import:0603-RES")
      (fields (field (name "MPN") "RC0603FR-130RL") (field (name "MANUFACTURER") "YAGEO"))
      (libsource (lib "eagle-import") (part "JUMPER_?_0603"))
    )
    (comp (ref "F_SELECT")
      (value "JUMPER_0603_")
      (footprint "eagle-import:0603-RES")
      (fields (field (name "MPN") "RC0603FR-130RL") (field (name "MANUFACTURER") "YAGEO"))
      (libsource (lib "eagle-import") (part "JUMPER_?_0603"))
    )
    (comp (ref "MAIN_CONNECTOR")
      (value "CONNECTOR-8_MF_T_V_BLACK")
      (footprint "eagle-import:MOLEX_MICROFIT_PTH_VERTICAL_08_DUAL")
      (fields (field (name "MANUFACTURER") "Molex") (field (name "MPN") "430450814"))
      (libsource (lib "eagle-import") (part "CONNECTOR-8_?_MF_T_VBLACK"))
    )
    (comp (ref "POWER")
      (value "CONNECTOR-2_MF_T_V_")
      (footprint "eagle-import:MOLEX_MICROFIT_PTH_VERTICAL_02_SINGLE")
      (fields (field (name "MANUFACTURER") "Molex") (field (name "MPN") "0436500217"))
      (libsource (lib "eagle-import") (part "CONNECTOR-2_?_MF_T_VBLACK"))
    )
    (comp (ref "R26")
      (value "RESISTOR_0603_100K")
      (footprint "eagle-import:0603-RES")
      (fields
        (field (name "MANUFACTURER") "Yageo")
        (field (name "MPN") "RC0603FR-07100KL")
        (field (name "POWER") "0.1W")
        (field (name "RESISTANCE") "100k")
      )
      (libsource (lib "eagle-import") (part "RESISTOR_?_0603100K"))
    )
    (comp (ref "R27")
      (value "RESISTOR_0603_10K")
      (footprint "eagle-import:0603-RES")
      (fields
        (field (name "MANUFACTURER") "Yageo")
        (field (name "MPN") "RC0603FR-0710KL")
        (field (name "POWER") "0.1W")
        (field (name "RESISTANCE") "10k")
      )
      (libsource (lib "eagle-import") (part "RESISTOR_?_060310K"))
    )
    (comp (ref "R28")
      (value "RESISTOR_0603_10K")
      (footprint "eagle-import:0603-RES")
      (fields
        (field (name "MANUFACTURER") "Yageo")
        (field (name "MPN") "RC0603FR-0710KL")
        (field (name "POWER") "0.1W")
        (field (name "RESISTANCE") "10k")
      )
      (libsource (lib "eagle-import") (part "RESISTOR_?_060310K"))
    )
    (comp (ref "R30")
      (value "RESISTOR_0603_10K")
      (footprint "eagle-import:0603-RES")
      (fields
        (field (name "MANUFACTURER") "Yageo")
        (field (name "MPN") "RC0603FR-0710KL")
        (field (name "POWER") "0.1W")
        (field (name "RESISTANCE") "10k")
      )
      (libsource (lib "eagle-import") (part "RESISTOR_?_060310K"))
    )
    (comp (ref "R39")
      (value "RESISTOR_0603_60.4")
      (footprint "eagle-import:0603-RES")
      (fields
        (field (name "MANUFACTURER") "Yageo")
        (field (name "MPN") "RC0603FR-0760R4L")
        (field (name "POWER") "0.1W")
        (field (name "RESISTANCE") "60.4")
      )
      (libsource (lib "eagle-import") (part "RESISTOR_?_060360.4"))
    )
    (comp (ref "R40")
      (value "RESISTOR_0603_60.4")
      (footprint "eagle-import:0603-RES")
      (fields
        (field (name "MANUFACTURER") "Yageo")
        (field (name "MPN") "RC0603FR-0760R4L")
        (field (name "POWER") "0.1W")
        (field (name "RESISTANCE") "60.4")
      )
      (libsource (lib "eagle-import") (part "RESISTOR_?_060360.4"))
    )
    (comp (ref "R100")
      (value "RESISTOR_0603_1K")
      (footprint "eagle-import:0603-RES")
      (fields
        (field (name "MANUFACTURER") "Yageo")
        (field (name "MPN") "RC0603FR-071KL")
        (field (name "POWER") "0.1W")
        (field (name "RESISTANCE") "1k")
      )
      (libsource (lib "eagle-import") (part "RESISTOR_?_06031K"))
    )
    (comp (ref "U1")
      (value "LOGICGATE_BUFFER")
      (footprint "eagle-import:SC-70-5")
      (fields (field (name "MANUFACTURER") "Texas Instruments"))
      (libsource (lib "eagle-import") (part "LOGICGATE_BUFFER"))
    )
    (comp (ref "U2")
      (value "ADM8316WBX30")
      (footprint "eagle-import:SOT-23-5")
      (fields (field (name "MANUFACTURER") "Analog Devices Inc.") (field (name "MPN") "ADM8316WBX30ARJZR7"))
      (libsource (lib "eagle-import") (part "ADM8316WBX30"))
    )
    (comp (ref "U3")
      (value "VOLTAGE_REGULATOR_MODULE_OKI-78SR_5V")
      (footprint "eagle-import:OKI-78SR")
      (fields
        (field (name "MANUFACTURER") "Murata Power Solutions Inc.")
        (field (name "MPN") "OKI-78SR-5/1.5-W36-C")
      )
      (libsource (lib "eagle-import") (part "VOLTAGE_REGULATOR_MODULE_?_OKI-78SR5V"))
    )
    (comp (ref "U100")
      (value "MCP2562FD")
      (footprint "eagle-import:SOIC-08(NARROW,0.15_)")
      (fields (field (name "MPN") "MCP2562FD-E/SN") (field (name "MANUFACTURER") "Microchip Technology"))
      (libsource (lib "eagle-import") (part "MCP2562FD"))
    )
    (comp (ref "U101")
      (value "MCP2562FD")
      (footprint "eagle-import:SOIC-08(NARROW,0.15_)")
      (fields (field (name "MPN") "MCP2562FD-E/SN") (field (name "MANUFACTURER") "Microchip Technology"))
      (libsource (lib "eagle-import") (part "MCP2562FD"))
    )
    (comp (ref "U102")
      (value "RELAY_SOLIDSTATE_NO")
      (footprint "eagle-import:DIP-4")
      (fields (field (name "MPN") "AQY214EHA") (field (name "MANUFACTURER") "AQY214EHA"))
      (libsource (lib "eagle-import") (part "RELAY_SOLIDSTATE_NO"))
    )
    (comp (ref "XB1")
      (value "BATTERY_HOLDER_KEYSTONE_498")
      (footprint "eagle-import:498")
      (fields (field (name "MPN") "498") (field (name "MANUFACTURER") "Keystone Electronics"))
      (libsource (lib "eagle-import") (part "BATTERY_HOLDER_KEYSTONE_498"))
    )
    (comp (ref "XF1")
      (value "FUSE_HOLDER_MINIBLADEPTH")
      (footprint "eagle-import:3568")
      (fields (field (name "MANUFACTURER") "Keystone") (field (name "MPN") "3568"))
      (libsource (lib "eagle-import") (part "FUSE_HOLDER_PTHMINIBLADE"))
    )
    (comp (ref "XF2")
      (value "FUSE_HOLDER_MINIBLADEPTH")
      (footprint "eagle-import:3568")
      (fields (field (name "MANUFACTURER") "Keystone") (field (name "MPN") "3568"))
      (libsource (lib "eagle-import") (part "FUSE_HOLDER_PTHMINIBLADE"))
    )
  )
  (nets
    (net (code "1") (name "+5V") (class "Default")
      (node (ref "5V_PWR") (pin "2") (pinfunction "A_2") (pintype "passive"))
      (node (ref "A1") (pin "VIN") (pinfunction "VIN_VIN") (pintype "power_in"))
      (node (ref "A2") (pin "VIN") (pinfunction "VIN_VIN") (pintype "power_in"))
      (node (ref "C101") (pin "2") (pinfunction "2_2") (pintype "passive"))
      (node (ref "C103") (pin "2") (pinfunction "2_2") (pintype "passive"))
      (node (ref "C4") (pin "2") (pinfunction "2_2") (pintype "passive"))
      (node (ref "C5") (pin "1") (pinfunction "1_1") (pintype "passive"))
      (node (ref "C6") (pin "1") (pinfunction "1_1") (pintype "passive"))
      (node (ref "LATCH") (pin "2") (pinfunction "A_2") (pintype "passive"))
      (node (ref "R38") (pin "1") (pinfunction "1_1") (pintype "passive"))
      (node (ref "TP11") (pin "1") (pinfunction "1_1") (pintype "passive"))
      (node (ref "U100") (pin "3") (pinfunction "VDD_3") (pintype "power_in"))
      (node (ref "U101") (pin "3") (pinfunction "VDD_3") (pintype "power_in"))
      (node (ref "U3") (pin "3") (pinfunction "OUT_3") (pintype "power_in"))
    )
    (net (code "2") (name "+12V") (class "Default")
      (node (ref "AUX_CAN") (pin "1") (pinfunction "+12V_1") (pintype "power_in"))
      (node (ref "C7") (pin "2") (pinfunction "2_2") (pintype "passive"))
      (node (ref "C8") (pin "1") (pinfunction "1_1") (pintype "passive"))
      (node (ref "C9") (pin "1") (pinfunction "1_1") (pintype "passive"))
      (node (ref "MAIN_CONNECTOR") (pin "4") (pinfunction "4_4") (pintype "passive"))
      (node (ref "R17") (pin "1") (pinfunction "1_1") (pintype "passive"))
      (node (ref "TP13") (pin "1") (pinfunction "1_1") (pintype "passive"))
      (node (ref "U$4") (pin "4") (pinfunction "CONTACT2_4") (pintype "bidirectional"))
      (node (ref "U3") (pin "1") (pinfunction "IN_1") (pintype "power_in"))
      (node (ref "XF1") (pin "3") (pinfunction "2_3") (pintype "passive"))
      (node (ref "XF1") (pin "4") (pinfunction "2_4") (pintype "passive"))
    )
    (net (code "3") (name "4.0_CRX") (class "Default")
      (node (ref "A2") (pin "D0") (pinfunction "(CRX1)D0_D0") (pintype "bidirectional"))
      (node (ref "A2") (pin "D4") (pinfunction "D4_D4") (pintype "bidirectional"))
      (node (ref "U100") (pin "4") (pinfunction "RXD_4") (pintype "output"))
    )
    (net (code "4") (name "4.0_CTX") (class "Default")
      (node (ref "A2") (pin "D1") (pinfunction "(CTX1)D1_D1") (pintype "bidirectional"))
      (node (ref "A2") (pin "D3") (pinfunction "D3_D3") (pintype "bidirectional"))
      (node (ref "U100") (pin "1") (pinfunction "TXD_1") (pintype "input"))
    )
    (net (code "5") (name "4.1_CRX") (class "Default")
      (node (ref "A1") (pin "D0") (pinfunction "(CRX1)D0_D0") (pintype "bidirectional"))
      (node (ref "A1") (pin "D4") (pinfunction "D4_D4") (pintype "bidirectional"))
      (node (ref "U101") (pin "4") (pinfunction "RXD_4") (pintype "output"))
    )
    (net (code "6") (name "4.1_CTX") (class "Default")
      (node (ref "A1") (pin "D1") (pinfunction "(CTX1)D1_D1") (pintype "bidirectional"))
      (node (ref "A1") (pin "D3") (pinfunction "D3_D3") (pintype "bidirectional"))
      (node (ref "U101") (pin "1") (pinfunction "TXD_1") (pintype "input"))
    )
    (net (code "7") (name "12V_READ") (class "Default")
      (node (ref "A1") (pin "D20") (pinfunction "A6_D20") (pintype "bidirectional"))
      (node (ref "A2") (pin "D20") (pinfunction "A6_D20") (pintype "bidirectional"))
      (node (ref "R17") (pin "2") (pinfunction "2_2") (pintype "passive"))
      (node (ref "R9") (pin "1") (pinfunction "1_1") (pintype "passive"))
    )
    (net (code "8") (name "BMS_OK") (class "Default")
      (node (ref "BMS_OK") (pin "2") (pinfunction "A_2") (pintype "passive"))
      (node (ref "D100") (pin "3") (pinfunction "C_3") (pintype "passive"))
      (node (ref "MAIN_CONNECTOR") (pin "6") (pinfunction "6_6") (pintype "passive"))
      (node (ref "R33") (pin "2") (pinfunction "2_2") (pintype "passive"))
      (node (ref "R34") (pin "2") (pinfunction "2_2") (pintype "passive"))
      (node (ref "TP3") (pin "1") (pinfunction "1_1") (pintype "passive"))
    )
    (net (code "9") (name "CANH") (class "Default")
      (node (ref "AUX_CAN") (pin "4") (pinfunction "CANH_4") (pintype "bidirectional"))
      (node (ref "CAN_TERM") (pin "2") (pinfunction "2_2") (pintype "passive"))
      (node (ref "CHG_CAN") (pin "4") (pinfunction "4_4") (pintype "passive"))
      (node (ref "D104") (pin "1") (pinfunction "C1_1") (pintype "passive"))
      (node (ref "MAIN_CONNECTOR") (pin "1") (pinfunction "1_1") (pintype "passive"))
      (node (ref "U100") (pin "7") (pinfunction "CANH_7") (pintype "bidirectional"))
      (node (ref "U101") (pin "7") (pinfunction "CANH_7") (pintype "bidirectional"))
    )
    (net (code "10") (name "CANL") (class "Default")
      (node (ref "AUX_CAN") (pin "3") (pinfunction "CANL_3") (pintype "bidirectional"))
      (node (ref "CHG_CAN") (pin "5") (pinfunction "5_5") (pintype "passive"))
      (node (ref "D104") (pin "2") (pinfunction "C2_2") (pintype "passive"))
      (node (ref "MAIN_CONNECTOR") (pin "2") (pinfunction "2_2") (pintype "passive"))
      (node (ref "R40") (pin "1") (pinfunction "1_1") (pintype "passive"))
      (node (ref "U100") (pin "6") (pinfunction "CANL_6") (pintype "bidirectional"))
      (node (ref "U101") (pin "6") (pinfunction "CANL_6") (pintype "bidirectional"))
    )
    (net (code "11") (name "CCU_OK") (class "Default")
      (node (ref "CCU_OK") (pin "2") (pinfunction "A_2") (pintype "passive"))
      (node (ref "R30") (pin "2") (pinfunction "2_2") (pintype "passive"))
      (node (ref "R31") (pin "2") (pinfunction "2_2") (pintype "passive"))
      (node (ref "TP1") (pin "1") (pinfunction "1_1") (pintype "passive"))
      (node (ref "U1") (pin "4") (pinfunction "OUT_4") (pintype "output"))
    )
    (net (code "12") (name "GND") (class "Default")
      (node (ref "A1") (pin "AGND/GND") (pinfunction "GND_AGND/GND") (pintype "bidirectional"))
      (node (ref "A1") (pin "GND") (pinfunction "GND_GND") (pintype "bidirectional"))
      (node (ref "A1") (pin "GND@2") (pinfunction "GND_GND@2") (pintype "bidirectional"))
      (node (ref "A2") (pin "AGND/GND") (pinfunction "GND_AGND/GND") (pintype "power_in"))
      (node (ref "A2") (pin "GND") (pinfunction "GND_GND") (pintype "power_in"))
      (node (ref "AUX_CAN") (pin "2") (pinfunction "GND_2") (pintype "power_in"))
      (node (ref "C1") (pin "1") (pinfunction "1_1") (pintype "passive"))
      (node (ref "C10") (pin "2") (pinfunction "2_2") (pintype "passive"))
      (node (ref "C100") (pin "1") (pinfunction "1_1") (pintype "passive"))
      (node (ref "C101") (pin "1") (pinfunction "1_1") (pintype "passive"))
      (node (ref "C102") (pin "1") (pinfunction "1_1") (pintype "passive"))
      (node (ref "C103") (pin "1") (pinfunction "1_1") (pintype "passive"))
      (node (ref "C2") (pin "1") (pinfunction "1_1") (pintype "passive"))
      (node (ref "C3") (pin "1") (pinfunction "1_1") (pintype "passive"))
      (node (ref "C4") (pin "1") (pinfunction "1_1") (pintype "passive"))
      (node (ref "C5") (pin "2") (pinfunction "2_2") (pintype "passive"))
      (node (ref "C6") (pin "2") (pinfunction "2_2") (pintype "passive"))
      (node (ref "C7") (pin "1") (pinfunction "1_1") (pintype "passive"))
      (node (ref "C8") (pin "2") (pinfunction "2_2") (pintype "passive"))
      (node (ref "C9") (pin "2") (pinfunction "2_2") (pintype "passive"))
      (node (ref "CHG_CAN") (pin "6") (pinfunction "6_6") (pintype "passive"))
      (node (ref "D100") (pin "1") (pinfunction "A_1") (pintype "passive"))
      (node (ref "D101") (pin "1") (pinfunction "A_1") (pintype "passive"))
      (node (ref "D104") (pin "3") (pinfunction "A_3") (pintype "passive"))
      (node (ref "D4") (pin "1") (pinfunction "A_1") (pintype "passive"))
      (node (ref "K1") (pin "14") (pinfunction "4_14") (pintype "bidirectional"))
      (node (ref "K2") (pin "14") (pinfunction "4_14") (pintype "bidirectional"))
      (node (ref "K3") (pin "14") (pinfunction "4_14") (pintype "bidirectional"))
      (node (ref "LATCH_BUTTON") (pin "3") (pinfunction "S_3") (pintype "passive"))
      (node (ref "LATCH_BUTTON") (pin "4") (pinfunction "S_4") (pintype "passive"))
      (node (ref "MAIN_CONNECTOR") (pin "3") (pinfunction "3_3") (pintype "passive"))
      (node (ref "POWER") (pin "2") (pinfunction "2_2") (pintype "passive"))
      (node (ref "R1") (pin "2") (pinfunction "2_2") (pintype "passive"))
      (node (ref "R10") (pin "2") (pinfunction "2_2") (pintype "passive"))
      (node (ref "R11") (pin "2") (pinfunction "2_2") (pintype "passive"))
      (node (ref "R12") (pin "2") (pinfunction "2_2") (pintype "passive"))
      (node (ref "R13") (pin "2") (pinfunction "2_2") (pintype "passive"))
      (node (ref "R14") (pin "2") (pinfunction "2_2") (pintype "passive"))
      (node (ref "R15") (pin "2") (pinfunction "2_2") (pintype "passive"))
      (node (ref "R2") (pin "2") (pinfunction "2_2") (pintype "passive"))
      (node (ref "R24") (pin "1") (pinfunction "1_1") (pintype "passive"))
      (node (ref "R26") (pin "2") (pinfunction "2_2") (pintype "passive"))
      (node (ref "R27") (pin "2") (pinfunction "2_2") (pintype "passive"))
      (node (ref "R28") (pin "1") (pinfunction "1_1") (pintype "passive"))
      (node (ref "R29") (pin "2") (pinfunction "2_2") (pintype "passive"))
      (node (ref "R3") (pin "2") (pinfunction "2_2") (pintype "passive"))
      (node (ref "R30") (pin "1") (pinfunction "1_1") (pintype "passive"))
      (node (ref "R32") (pin "2") (pinfunction "2_2") (pintype "passive"))
      (node (ref "R33") (pin "1") (pinfunction "1_1") (pintype "passive"))
      (node (ref "R36") (pin "1") (pinfunction "1_1") (pintype "passive"))
      (node (ref "R4") (pin "2") (pinfunction "2_2") (pintype "passive"))
      (node (ref "R8") (pin "2") (pinfunction "2_2") (pintype "passive"))
      (node (ref "R9") (pin "2") (pinfunction "2_2") (pintype "passive"))
      (node (ref "SHDN_B") (pin "1") (pinfunction "C_1") (pintype "passive"))
      (node (ref "SHDN_C") (pin "1") (pinfunction "C_1") (pintype "passive"))
      (node (ref "SHDN_D") (pin "1") (pinfunction "C_1") (pintype "passive"))
      (node (ref "SHDN_E") (pin "1") (pinfunction "C_1") (pintype "passive"))
      (node (ref "TP12") (pin "1") (pinfunction "1_1") (pintype "passive"))
      (node (ref "U$4") (pin "2") (pinfunction "CONTROL-_2") (pintype "passive"))
      (node (ref "U1") (pin "3") (pinfunction "GND_3") (pintype "power_in"))
      (node (ref "U100") (pin "2") (pinfunction "GND_2") (pintype "power_in"))
      (node (ref "U100") (pin "8") (pinfunction "STBY_8") (pintype "passive"))
      (node (ref "U101") (pin "2") (pinfunction "GND_2") (pintype "power_in"))
      (node (ref "U101") (pin "8") (pinfunction "STBY_8") (pintype "passive"))
      (node (ref "U102") (pin "2") (pinfunction "CONTROL-_2") (pintype "passive"))
      (node (ref "U102") (pin "3") (pinfunction "CONTACT1_3") (pintype "bidirectional"))
      (node (ref "U2") (pin "2") (pinfunction "GND_2") (pintype "power_in"))
      (node (ref "U3") (pin "2") (pinfunction "GND_2") (pintype "power_in"))
      (node (ref "XB1") (pin "2") (pinfunction "MINUS_2") (pintype "power_in"))
    )
    (net (code "13") (name "IMD_OK") (class "Default")
      (node (ref "D101") (pin "3") (pinfunction "C_3") (pintype "passive"))
      (node (ref "MAIN_CONNECTOR") (pin "5") (pinfunction "5_5") (pintype "passive"))
      (node (ref "OKHS") (pin "2") (pinfunction "A_2") (pintype "passive"))
      (node (ref "R24") (pin "2") (pinfunction "2_2") (pintype "passive"))
      (node (ref "R25") (pin "2") (pinfunction "2_2") (pintype "passive"))
      (node (ref "TP2") (pin "1") (pinfunction "1_1") (pintype "passive"))
    )
    (net (code "14") (name "LATCH_BUTTON") (class "Default")
      (node (ref "D1") (pin "C") (pinfunction "C_C") (pintype "passive"))
      (node (ref "D2") (pin "C") (pinfunction "C_C") (pintype "passive"))
      (node (ref "D3") (pin "C") (pinfunction "C_C") (pintype "passive"))
      (node (ref "LATCH_BUTTON") (pin "1") (pinfunction "P_1") (pintype "passive"))
      (node (ref "LATCH_BUTTON") (pin "2") (pinfunction "P_2") (pintype "passive"))
      (node (ref "R35") (pin "2") (pinfunction "2_2") (pintype "passive"))
      (node (ref "R38") (pin "2") (pinfunction "2_2") (pintype "passive"))
    )
    (net (code "15") (name "Net-(4.1_ONLY-Pad1)") (class "Default")
      (node (ref "4.1_ONLY") (pin "1") (pinfunction "1_1") (pintype "passive"))
      (node (ref "A1") (pin "3V3") (pinfunction "3.3V_3V3") (pintype "power_in"))
      (node (ref "A1") (pin "3V3@2") (pinfunction "3.3V_3V3@2") (pintype "power_in"))
      (node (ref "A1") (pin "3V3@3") (pinfunction "3.3V_3V3@3") (pintype "power_in"))
    )
    (net (code "16") (name "Net-(5V_PWR-C)") (class "Default")
      (node (ref "5V_PWR") (pin "1") (pinfunction "C_1") (pintype "passive"))
      (node (ref "R32") (pin "1") (pinfunction "1_1") (pintype "passive"))
    )
    (net (code "17") (name "Net-(BMS_OK-C)") (class "Default")
      (node (ref "BMS_OK") (pin "1") (pinfunction "C_1") (pintype "passive"))
      (node (ref "R3") (pin "1") (pinfunction "1_1") (pintype "passive"))
    )
    (net (code "18") (name "Net-(C10-Pad1)") (class "Default")
      (node (ref "C10") (pin "1") (pinfunction "1_1") (pintype "passive"))
      (node (ref "R39") (pin "1") (pinfunction "1_1") (pintype "passive"))
      (node (ref "R40") (pin "2") (pinfunction "2_2") (pintype "passive"))
    )
    (net (code "19") (name "Net-(CAN_TERM-Pad1)") (class "Default")
      (node (ref "CAN_TERM") (pin "1") (pinfunction "1_1") (pintype "passive"))
      (node (ref "R39") (pin "2") (pinfunction "2_2") (pintype "passive"))
    )
    (net (code "20") (name "Net-(CCU_OK-C)") (class "Default")
      (node (ref "CCU_OK") (pin "1") (pinfunction "C_1") (pintype "passive"))
      (node (ref "R1") (pin "1") (pinfunction "1_1") (pintype "passive"))
    )
    (net (code "21") (name "Net-(D4-C)") (class "Default")
      (node (ref "D4") (pin "3") (pinfunction "C_3") (pintype "passive"))
      (node (ref "POWER") (pin "1") (pinfunction "1_1") (pintype "passive"))
      (node (ref "XF1") (pin "1") (pinfunction "1_1") (pintype "passive"))
      (node (ref "XF1") (pin "2") (pinfunction "1_2") (pintype "passive"))
      (node (ref "XF2") (pin "1") (pinfunction "1_1") (pintype "passive"))
      (node (ref "XF2") (pin "2") (pinfunction "1_2") (pintype "passive"))
    )
    (net (code "22") (name "Net-(E_SELECT-Pad2)") (class "Default")
      (node (ref "E_SELECT") (pin "2") (pinfunction "2_2") (pintype "passive"))
      (node (ref "F_SELECT") (pin "2") (pinfunction "2_2") (pintype "passive"))
      (node (ref "R100") (pin "1") (pinfunction "1_1") (pintype "passive"))
    )
    (net (code "23") (name "Net-(K1-3)") (class "Default")
      (node (ref "D1") (pin "A") (pinfunction "A_A") (pintype "passive"))
      (node (ref "D105") (pin "A") (pinfunction "A_A") (pintype "passive"))
      (node (ref "K1") (pin "11") (pinfunction "3_11") (pintype "bidirectional"))
      (node (ref "K1") (pin "A2") (pinfunction "COIL-_A2") (pintype "bidirectional"))
    )
    (net (code "24") (name "Net-(K1-COIL+)") (class "Default")
      (node (ref "D105") (pin "C") (pinfunction "C_C") (pintype "passive"))
      (node (ref "K1") (pin "A1") (pinfunction "COIL+_A1") (pintype "bidirectional"))
      (node (ref "R25") (pin "1") (pinfunction "1_1") (pintype "passive"))
    )
    (net (code "25") (name "Net-(K2-3)") (class "Default")
      (node (ref "D103") (pin "A") (pinfunction "A_A") (pintype "passive"))
      (node (ref "D2") (pin "A") (pinfunction "A_A") (pintype "passive"))
      (node (ref "K2") (pin "11") (pinfunction "3_11") (pintype "bidirectional"))
      (node (ref "K2") (pin "A2") (pinfunction "COIL-_A2") (pintype "bidirectional"))
    )
    (net (code "26") (name "Net-(K2-COIL+)") (class "Default")
      (node (ref "D103") (pin "C") (pinfunction "C_C") (pintype "passive"))
      (node (ref "K2") (pin "A1") (pinfunction "COIL+_A1") (pintype "bidirectional"))
      (node (ref "R34") (pin "1") (pinfunction "1_1") (pintype "passive"))
    )
    (net (code "27") (name "Net-(K3-3)") (class "Default")
      (node (ref "D102") (pin "A") (pinfunction "A_A") (pintype "passive"))
      (node (ref "D3") (pin "A") (pinfunction "A_A") (pintype "passive"))
      (node (ref "K3") (pin "11") (pinfunction "3_11") (pintype "bidirectional"))
      (node (ref "K3") (pin "A2") (pinfunction "COIL-_A2") (pintype "bidirectional"))
    )
    (net (code "28") (name "Net-(K3-COIL+)") (class "Default")
      (node (ref "D102") (pin "C") (pinfunction "C_C") (pintype "passive"))
      (node (ref "K3") (pin "A1") (pinfunction "COIL+_A1") (pintype "bidirectional"))
      (node (ref "R37") (pin "1") (pinfunction "1_1") (pintype "passive"))
    )
    (net (code "29") (name "Net-(LATCH-C)") (class "Default")
      (node (ref "LATCH") (pin "1") (pinfunction "C_1") (pintype "passive"))
      (node (ref "R35") (pin "1") (pinfunction "1_1") (pintype "passive"))
    )
    (net (code "30") (name "Net-(OKHS-C)") (class "Default")
      (node (ref "OKHS") (pin "1") (pinfunction "C_1") (pintype "passive"))
      (node (ref "R2") (pin "1") (pinfunction "1_1") (pintype "passive"))
    )
    (net (code "31") (name "Net-(SHDN_B-A)") (class "Default")
      (node (ref "R16") (pin "2") (pinfunction "2_2") (pintype "passive"))
      (node (ref "SHDN_B") (pin "2") (pinfunction "A_2") (pintype "passive"))
    )
    (net (code "32") (name "Net-(SHDN_C-A)") (class "Default")
      (node (ref "R7") (pin "2") (pinfunction "2_2") (pintype "passive"))
      (node (ref "SHDN_C") (pin "2") (pinfunction "A_2") (pintype "passive"))
    )
    (net (code "33") (name "Net-(SHDN_D-A)") (class "Default")
      (node (ref "R6") (pin "2") (pinfunction "2_2") (pintype "passive"))
      (node (ref "SHDN_D") (pin "2") (pinfunction "A_2") (pintype "passive"))
    )
    (net (code "34") (name "Net-(SHDN_E-A)") (class "Default")
      (node (ref "R5") (pin "2") (pinfunction "2_2") (pintype "passive"))
      (node (ref "SHDN_E") (pin "2") (pinfunction "A_2") (pintype "passive"))
    )
    (net (code "35") (name "Net-(SHDN_F-C)") (class "Default")
      (node (ref "R4") (pin "1") (pinfunction "1_1") (pintype "passive"))
      (node (ref "SHDN_F") (pin "1") (pinfunction "C_1") (pintype "passive"))
    )
    (net (code "36") (name "Net-(STATUS_4.1-C)") (class "Default")
      (node (ref "R8") (pin "1") (pinfunction "1_1") (pintype "passive"))
      (node (ref "STATUS_4.1") (pin "1") (pinfunction "C_1") (pintype "passive"))
    )
    (net (code "37") (name "Net-(STATUS_4.2-C)") (class "Default")
      (node (ref "R29") (pin "1") (pinfunction "1_1") (pintype "passive"))
      (node (ref "STATUS_4.2") (pin "1") (pinfunction "C_1") (pintype "passive"))
    )
    (net (code "38") (name "Net-(U$4-CONTACT1)") (class "Default")
      (node (ref "R36") (pin "2") (pinfunction "2_2") (pintype "passive"))
      (node (ref "R37") (pin "2") (pinfunction "2_2") (pintype "passive"))
      (node (ref "U$4") (pin "3") (pinfunction "CONTACT1_3") (pintype "bidirectional"))
    )
    (net (code "39") (name "Net-(U$4-CONTROL+)") (class "Default")
      (node (ref "R31") (pin "1") (pinfunction "1_1") (pintype "passive"))
      (node (ref "U$4") (pin "1") (pinfunction "CONTROL+_1") (pintype "passive"))
    )
    (net (code "40") (name "Net-(U1A-IN)") (class "Default")
      (node (ref "R26") (pin "1") (pinfunction "1_1") (pintype "passive"))
      (node (ref "U1") (pin "2") (pinfunction "IN_2") (pintype "input"))
      (node (ref "U2") (pin "1") (pinfunction "~{RESET}_1") (pintype "output"))
    )
    (net (code "41") (name "Net-(U102-CONTROL+)") (class "Default")
      (node (ref "R100") (pin "2") (pinfunction "2_2") (pintype "passive"))
      (node (ref "U102") (pin "1") (pinfunction "CONTROL+_1") (pintype "passive"))
    )
    (net (code "42") (name "Net-(XB1-PLUS)") (class "Default")
      (node (ref "A1") (pin "VBAT") (pinfunction "VBAT_VBAT") (pintype "power_in"))
      (node (ref "XB1") (pin "1") (pinfunction "PLUS_1") (pintype "power_in"))
    )
    (net (code "43") (name "RPC_SWITCH") (class "Default")
      (node (ref "MAIN_CONNECTOR") (pin "8") (pinfunction "8_8") (pintype "passive"))
      (node (ref "U102") (pin "4") (pinfunction "CONTACT2_4") (pintype "bidirectional"))
    )
    (net (code "44") (name "SHDN_A") (class "Default")
      (node (ref "K1") (pin "21") (pinfunction "6_21") (pintype "bidirectional"))
      (node (ref "R23") (pin "1") (pinfunction "1_1") (pintype "passive"))
      (node (ref "TP8") (pin "1") (pinfunction "1_1") (pintype "passive"))
      (node (ref "XF2") (pin "3") (pinfunction "2_3") (pintype "passive"))
      (node (ref "XF2") (pin "4") (pinfunction "2_4") (pintype "passive"))
    )
    (net (code "45") (name "SHDN_A_READ") (class "Default")
      (node (ref "A1") (pin "D14") (pinfunction "A0_D14") (pintype "bidirectional"))
      (node (ref "A2") (pin "D14") (pinfunction "A0_D14") (pintype "bidirectional"))
      (node (ref "R15") (pin "1") (pinfunction "1_1") (pintype "passive"))
      (node (ref "R23") (pin "2") (pinfunction "2_2") (pintype "passive"))
    )
    (net (code "46") (name "SHDN_B") (class "Default")
      (node (ref "K1") (pin "24") (pinfunction "5_24") (pintype "bidirectional"))
      (node (ref "K2") (pin "21") (pinfunction "6_21") (pintype "bidirectional"))
      (node (ref "R16") (pin "1") (pinfunction "1_1") (pintype "passive"))
      (node (ref "R22") (pin "1") (pinfunction "1_1") (pintype "passive"))
      (node (ref "TP9") (pin "1") (pinfunction "1_1") (pintype "passive"))
    )
    (net (code "47") (name "SHDN_B_READ") (class "Default")
      (node (ref "A1") (pin "D15") (pinfunction "A1_D15") (pintype "bidirectional"))
      (node (ref "A2") (pin "D15") (pinfunction "A1_D15") (pintype "bidirectional"))
      (node (ref "R14") (pin "1") (pinfunction "1_1") (pintype "passive"))
      (node (ref "R22") (pin "2") (pinfunction "2_2") (pintype "passive"))
    )
    (net (code "48") (name "SHDN_C") (class "Default")
      (node (ref "K2") (pin "24") (pinfunction "5_24") (pintype "bidirectional"))
      (node (ref "K3") (pin "21") (pinfunction "6_21") (pintype "bidirectional"))
      (node (ref "R21") (pin "1") (pinfunction "1_1") (pintype "passive"))
      (node (ref "R7") (pin "1") (pinfunction "1_1") (pintype "passive"))
      (node (ref "TP7") (pin "1") (pinfunction "1_1") (pintype "passive"))
    )
    (net (code "49") (name "SHDN_C_READ") (class "Default")
      (node (ref "A1") (pin "D16") (pinfunction "A2_D16") (pintype "bidirectional"))
      (node (ref "A2") (pin "D16") (pinfunction "A2_D16") (pintype "bidirectional"))
      (node (ref "R13") (pin "1") (pinfunction "1_1") (pintype "passive"))
      (node (ref "R21") (pin "2") (pinfunction "2_2") (pintype "passive"))
    )
    (net (code "50") (name "SHDN_D") (class "Default")
      (node (ref "K3") (pin "24") (pinfunction "5_24") (pintype "bidirectional"))
      (node (ref "R20") (pin "1") (pinfunction "1_1") (pintype "passive"))
      (node (ref "R6") (pin "1") (pinfunction "1_1") (pintype "passive"))
      (node (ref "SHDN_BTN") (pin "1") (pinfunction "1_1") (pintype "passive"))
      (node (ref "TP6") (pin "1") (pinfunction "1_1") (pintype "passive"))
    )
    (net (code "51") (name "SHDN_D_READ") (class "Default")
      (node (ref "A1") (pin "D17") (pinfunction "A3_D17") (pintype "bidirectional"))
      (node (ref "A2") (pin "D17") (pinfunction "A3_D17") (pintype "bidirectional"))
      (node (ref "R12") (pin "1") (pinfunction "1_1") (pintype "passive"))
      (node (ref "R20") (pin "2") (pinfunction "2_2") (pintype "passive"))
    )
    (net (code "52") (name "SHDN_E") (class "Default")
      (node (ref "CHG_CAN") (pin "3") (pinfunction "3_3") (pintype "passive"))
      (node (ref "E_SELECT") (pin "1") (pinfunction "1_1") (pintype "passive"))
      (node (ref "R19") (pin "1") (pinfunction "1_1") (pintype "passive"))
      (node (ref "R5") (pin "1") (pinfunction "1_1") (pintype "passive"))
      (node (ref "SHDN_BTN") (pin "2") (pinfunction "2_2") (pintype "passive"))
      (node (ref "TP5") (pin "1") (pinfunction "1_1") (pintype "passive"))
    )
    (net (code "53") (name "SHDN_E_READ") (class "Default")
      (node (ref "A1") (pin "D18") (pinfunction "A4_D18") (pintype "bidirectional"))
      (node (ref "A2") (pin "D18") (pinfunction "A4_D18") (pintype "bidirectional"))
      (node (ref "R11") (pin "1") (pinfunction "1_1") (pintype "passive"))
      (node (ref "R19") (pin "2") (pinfunction "2_2") (pintype "passive"))
    )
    (net (code "54") (name "SHDN_F") (class "Default")
      (node (ref "CHG_CAN") (pin "1") (pinfunction "1_1") (pintype "passive"))
      (node (ref "CHG_CAN") (pin "2") (pinfunction "2_2") (pintype "passive"))
      (node (ref "F_SELECT") (pin "1") (pinfunction "1_1") (pintype "passive"))
      (node (ref "MAIN_CONNECTOR") (pin "7") (pinfunction "7_7") (pintype "passive"))
      (node (ref "R18") (pin "1") (pinfunction "1_1") (pintype "passive"))
      (node (ref "SHDN_F") (pin "2") (pinfunction "A_2") (pintype "passive"))
      (node (ref "TP4") (pin "1") (pinfunction "1_1") (pintype "passive"))
    )
    (net (code "55") (name "SHDN_F_READ") (class "Default")
      (node (ref "A1") (pin "D19") (pinfunction "A5_D19") (pintype "bidirectional"))
      (node (ref "A2") (pin "D19") (pinfunction "A5_D19") (pintype "bidirectional"))
      (node (ref "R10") (pin "1") (pinfunction "1_1") (pintype "passive"))
      (node (ref "R18") (pin "2") (pinfunction "2_2") (pintype "passive"))
    )
    (net (code "56") (name "STATUS_4.0") (class "Default")
      (node (ref "A2") (pin "D5") (pinfunction "D5_D5") (pintype "bidirectional"))
      (node (ref "STATUS_4.2") (pin "2") (pinfunction "A_2") (pintype "passive"))
    )
    (net (code "57") (name "STATUS_4.1") (class "Default")
      (node (ref "A1") (pin "D5") (pinfunction "D5_D5") (pintype "bidirectional"))
      (node (ref "STATUS_4.1") (pin "2") (pinfunction "A_2") (pintype "passive"))
    )
    (net (code "58") (name "SW_SHUTDOWN") (class "Default")
      (node (ref "A1") (pin "D6") (pinfunction "D6_D6") (pintype "bidirectional"))
      (node (ref "A2") (pin "D6") (pinfunction "D6_D6") (pintype "bidirectional"))
      (node (ref "C1") (pin "2") (pinfunction "2_2") (pintype "passive"))
      (node (ref "R28") (pin "2") (pinfunction "2_2") (pintype "passive"))
      (node (ref "U2") (pin "3") (pinfunction "~{MR}_3") (pintype "input"))
    )
    (net (code "59") (name "VDD") (class "Default")
      (node (ref "4.1_ONLY") (pin "2") (pinfunction "2_2") (pintype "passive"))
      (node (ref "A2") (pin "3.3V") (pinfunction "3.3V_3.3V") (pintype "power_in"))
      (node (ref "C100") (pin "2") (pinfunction "2_2") (pintype "passive"))
      (node (ref "C102") (pin "2") (pinfunction "2_2") (pintype "passive"))
      (node (ref "C2") (pin "2") (pinfunction "2_2") (pintype "passive"))
      (node (ref "C3") (pin "2") (pinfunction "2_2") (pintype "passive"))
      (node (ref "TP10") (pin "1") (pinfunction "1_1") (pintype "passive"))
      (node (ref "U1") (pin "5") (pinfunction "VDD_5") (pintype "power_in"))
      (node (ref "U100") (pin "5") (pinfunction "VIO_5") (pintype "power_in"))
      (node (ref "U101") (pin "5") (pinfunction "VIO_5") (pintype "power_in"))
      (node (ref "U2") (pin "5") (pinfunction "VDD_5") (pintype "power_in"))
    )
    (net (code "60") (name "WATCHDOG_IN") (class "Default")
      (node (ref "A1") (pin "D7") (pinfunction "D7_D7") (pintype "bidirectional"))
      (node (ref "A2") (pin "D7") (pinfunction "D7_D7") (pintype "bidirectional"))
      (node (ref "R27") (pin "1") (pinfunction "1_1") (pintype "passive"))
      (node (ref "U2") (pin "4") (pinfunction "WDI_4") (pintype "input"))
    )
    (net (code "61") (name "unconnected-(A1-(CLK)D13-PadD13)") (class "Default")
      (node (ref "A1") (pin "D13") (pinfunction "(CLK)D13_D13") (pintype "bidirectional"))
    )
    (net (code "62") (name "unconnected-(A1-(CS)D10-PadD10)") (class "Default")
      (node (ref "A1") (pin "D10") (pinfunction "(CS)D10_D10") (pintype "bidirectional"))
    )
    (net (code "63") (name "unconnected-(A1-(SDI)D12-PadD12)") (class "Default")
      (node (ref "A1") (pin "D12") (pinfunction "(SDI)D12_D12") (pintype "bidirectional"))
    )
    (net (code "64") (name "unconnected-(A1-(SDO)D11-PadD11)") (class "Default")
      (node (ref "A1") (pin "D11") (pinfunction "(SDO)D11_D11") (pintype "bidirectional"))
    )
    (net (code "65") (name "unconnected-(A1-A7-PadD21)") (class "Default")
      (node (ref "A1") (pin "D21") (pinfunction "A7_D21") (pintype "bidirectional"))
    )
    (net (code "66") (name "unconnected-(A1-A8-PadD22)") (class "Default")
      (node (ref "A1") (pin "D22") (pinfunction "A8_D22") (pintype "bidirectional"))
    )
    (net (code "67") (name "unconnected-(A1-A9-PadD23)") (class "Default")
      (node (ref "A1") (pin "D23") (pinfunction "A9_D23") (pintype "bidirectional"))
    )
    (net (code "68") (name "unconnected-(A1-A10-PadD24)") (class "Default")
      (node (ref "A1") (pin "D24") (pinfunction "A10_D24") (pintype "bidirectional"))
    )
    (net (code "69") (name "unconnected-(A1-A11-PadD25)") (class "Default")
      (node (ref "A1") (pin "D25") (pinfunction "A11_D25") (pintype "bidirectional"))
    )
    (net (code "70") (name "unconnected-(A1-A12-PadD26)") (class "Default")
      (node (ref "A1") (pin "D26") (pinfunction "A12_D26") (pintype "bidirectional"))
    )
    (net (code "71") (name "unconnected-(A1-A13-PadD27)") (class "Default")
      (node (ref "A1") (pin "D27") (pinfunction "A13_D27") (pintype "bidirectional"))
    )
    (net (code "72") (name "unconnected-(A1-A14-PadD38)") (class "Default")
      (node (ref "A1") (pin "D38") (pinfunction "A14_D38") (pintype "bidirectional"))
    )
    (net (code "73") (name "unconnected-(A1-A15-PadD39)") (class "Default")
      (node (ref "A1") (pin "D39") (pinfunction "A15_D39") (pintype "bidirectional"))
    )
    (net (code "74") (name "unconnected-(A1-A16-PadD40)") (class "Default")
      (node (ref "A1") (pin "D40") (pinfunction "A16_D40") (pintype "bidirectional"))
    )
    (net (code "75") (name "unconnected-(A1-A17-PadD41)") (class "Default")
      (node (ref "A1") (pin "D41") (pinfunction "A17_D41") (pintype "bidirectional"))
    )
    (net (code "76") (name "unconnected-(A1-PadD2)") (class "Default")
      (node (ref "A1") (pin "D2") (pinfunction "D2_D2") (pintype "bidirectional"))
    )
    (net (code "77") (name "unconnected-(A1-PadD8)") (class "Default")
      (node (ref "A1") (pin "D8") (pinfunction "D8_D8") (pintype "bidirectional"))
    )
    (net (code "78") (name "unconnected-(A1-PadD9)") (class "Default")
      (node (ref "A1") (pin "D9") (pinfunction "D9_D9") (pintype "bidirectional"))
    )
    (net (code "79") (name "unconnected-(A1-PadD28)") (class "Default")
      (node (ref "A1") (pin "D28") (pinfunction "D28_D28") (pintype "bidirectional"))
    )
    (net (code "80") (name "unconnected-(A1-PadD29)") (class "Default")
      (node (ref "A1") (pin "D29") (pinfunction "D29_D29") (pintype "bidirectional"))
    )
    (net (code "81") (name "unconnected-(A1-PadD30)") (class "Default")
      (node (ref "A1") (pin "D30") (pinfunction "D30_D30") (pintype "bidirectional"))
    )
    (net (code "82") (name "unconnected-(A1-PadD31)") (class "Default")
      (node (ref "A1") (pin "D31") (pinfunction "D31_D31") (pintype "bidirectional"))
    )
    (net (code "83") (name "unconnected-(A1-PadD32)") (class "Default")
      (node (ref "A1") (pin "D32") (pinfunction "D32_D32") (pintype "bidirectional"))
    )
    (net (code "84") (name "unconnected-(A1-PadD33)") (class "Default")
      (node (ref "A1") (pin "D33") (pinfunction "D33_D33") (pintype "bidirectional"))
    )
    (net (code "85") (name "unconnected-(A1-PadD34)") (class "Default")
      (node (ref "A1") (pin "D34") (pinfunction "D34_D34") (pintype "bidirectional"))
    )
    (net (code "86") (name "unconnected-(A1-PadD35)") (class "Default")
      (node (ref "A1") (pin "D35") (pinfunction "D35_D35") (pintype "bidirectional"))
    )
    (net (code "87") (name "unconnected-(A1-PadD36)") (class "Default")
      (node (ref "A1") (pin "D36") (pinfunction "D36_D36") (pintype "bidirectional"))
    )
    (net (code "88") (name "unconnected-(A1-PadD37)") (class "Default")
      (node (ref "A1") (pin "D37") (pinfunction "D37_D37") (pintype "bidirectional"))
    )
    (net (code "89") (name "unconnected-(A2-(CLK)D13-PadD13)") (class "Default")
      (node (ref "A2") (pin "D13") (pinfunction "(CLK)D13_D13") (pintype "bidirectional"))
    )
    (net (code "90") (name "unconnected-(A2-(CS)D10-PadD10)") (class "Default")
      (node (ref "A2") (pin "D10") (pinfunction "(CS)D10_D10") (pintype "bidirectional"))
    )
    (net (code "91") (name "unconnected-(A2-(SDI)D12-PadD12)") (class "Default")
      (node (ref "A2") (pin "D12") (pinfunction "(SDI)D12_D12") (pintype "bidirectional"))
    )
    (net (code "92") (name "unconnected-(A2-(SDO)D11-PadD11)") (class "Default")
      (node (ref "A2") (pin "D11") (pinfunction "(SDO)D11_D11") (pintype "bidirectional"))
    )
    (net (code "93") (name "unconnected-(A2-A7-PadD21)") (class "Default")
      (node (ref "A2") (pin "D21") (pinfunction "A7_D21") (pintype "bidirectional"))
    )
    (net (code "94") (name "unconnected-(A2-A8-PadD22)") (class "Default")
      (node (ref "A2") (pin "D22") (pinfunction "A8_D22") (pintype "bidirectional"))
    )
    (net (code "95") (name "unconnected-(A2-A9-PadD23)") (class "Default")
      (node (ref "A2") (pin "D23") (pinfunction "A9_D23") (pintype "bidirectional"))
    )
    (net (code "96") (name "unconnected-(A2-PadD2)") (class "Default")
      (node (ref "A2") (pin "D2") (pinfunction "D2_D2") (pintype "bidirectional"))
    )
    (net (code "97") (name "unconnected-(A2-PadD8)") (class "Default")
      (node (ref "A2") (pin "D8") (pinfunction "D8_D8") (pintype "bidirectional"))
    )
    (net (code "98") (name "unconnected-(A2-PadD9)") (class "Default")
      (node (ref "A2") (pin "D9") (pinfunction "D9_D9") (pintype "bidirectional"))
    )
    (net (code "99") (name "unconnected-(K1-2-Pad12)") (class "Default")
      (node (ref "K1") (pin "12") (pinfunction "2_12") (pintype "bidirectional"))
    )
    (net (code "100") (name "unconnected-(K1-7-Pad22)") (class "Default")
      (node (ref "K1") (pin "22") (pinfunction "7_22") (pintype "bidirectional"))
    )
    (net (code "101") (name "unconnected-(K2-2-Pad12)") (class "Default")
      (node (ref "K2") (pin "12") (pinfunction "2_12") (pintype "bidirectional"))
    )
    (net (code "102") (name "unconnected-(K2-7-Pad22)") (class "Default")
      (node (ref "K2") (pin "22") (pinfunction "7_22") (pintype "bidirectional"))
    )
    (net (code "103") (name "unconnected-(K3-2-Pad12)") (class "Default")
      (node (ref "K3") (pin "12") (pinfunction "2_12") (pintype "bidirectional"))
    )
    (net (code "104") (name "unconnected-(K3-7-Pad22)") (class "Default")
      (node (ref "K3") (pin "22") (pinfunction "7_22") (pintype "bidirectional"))
    )
  )
)
